# axiom_beta_sensor_cmv12000_v0_9_a57a812d.net
KiCad netlist of a schematic drawn in EAGLE
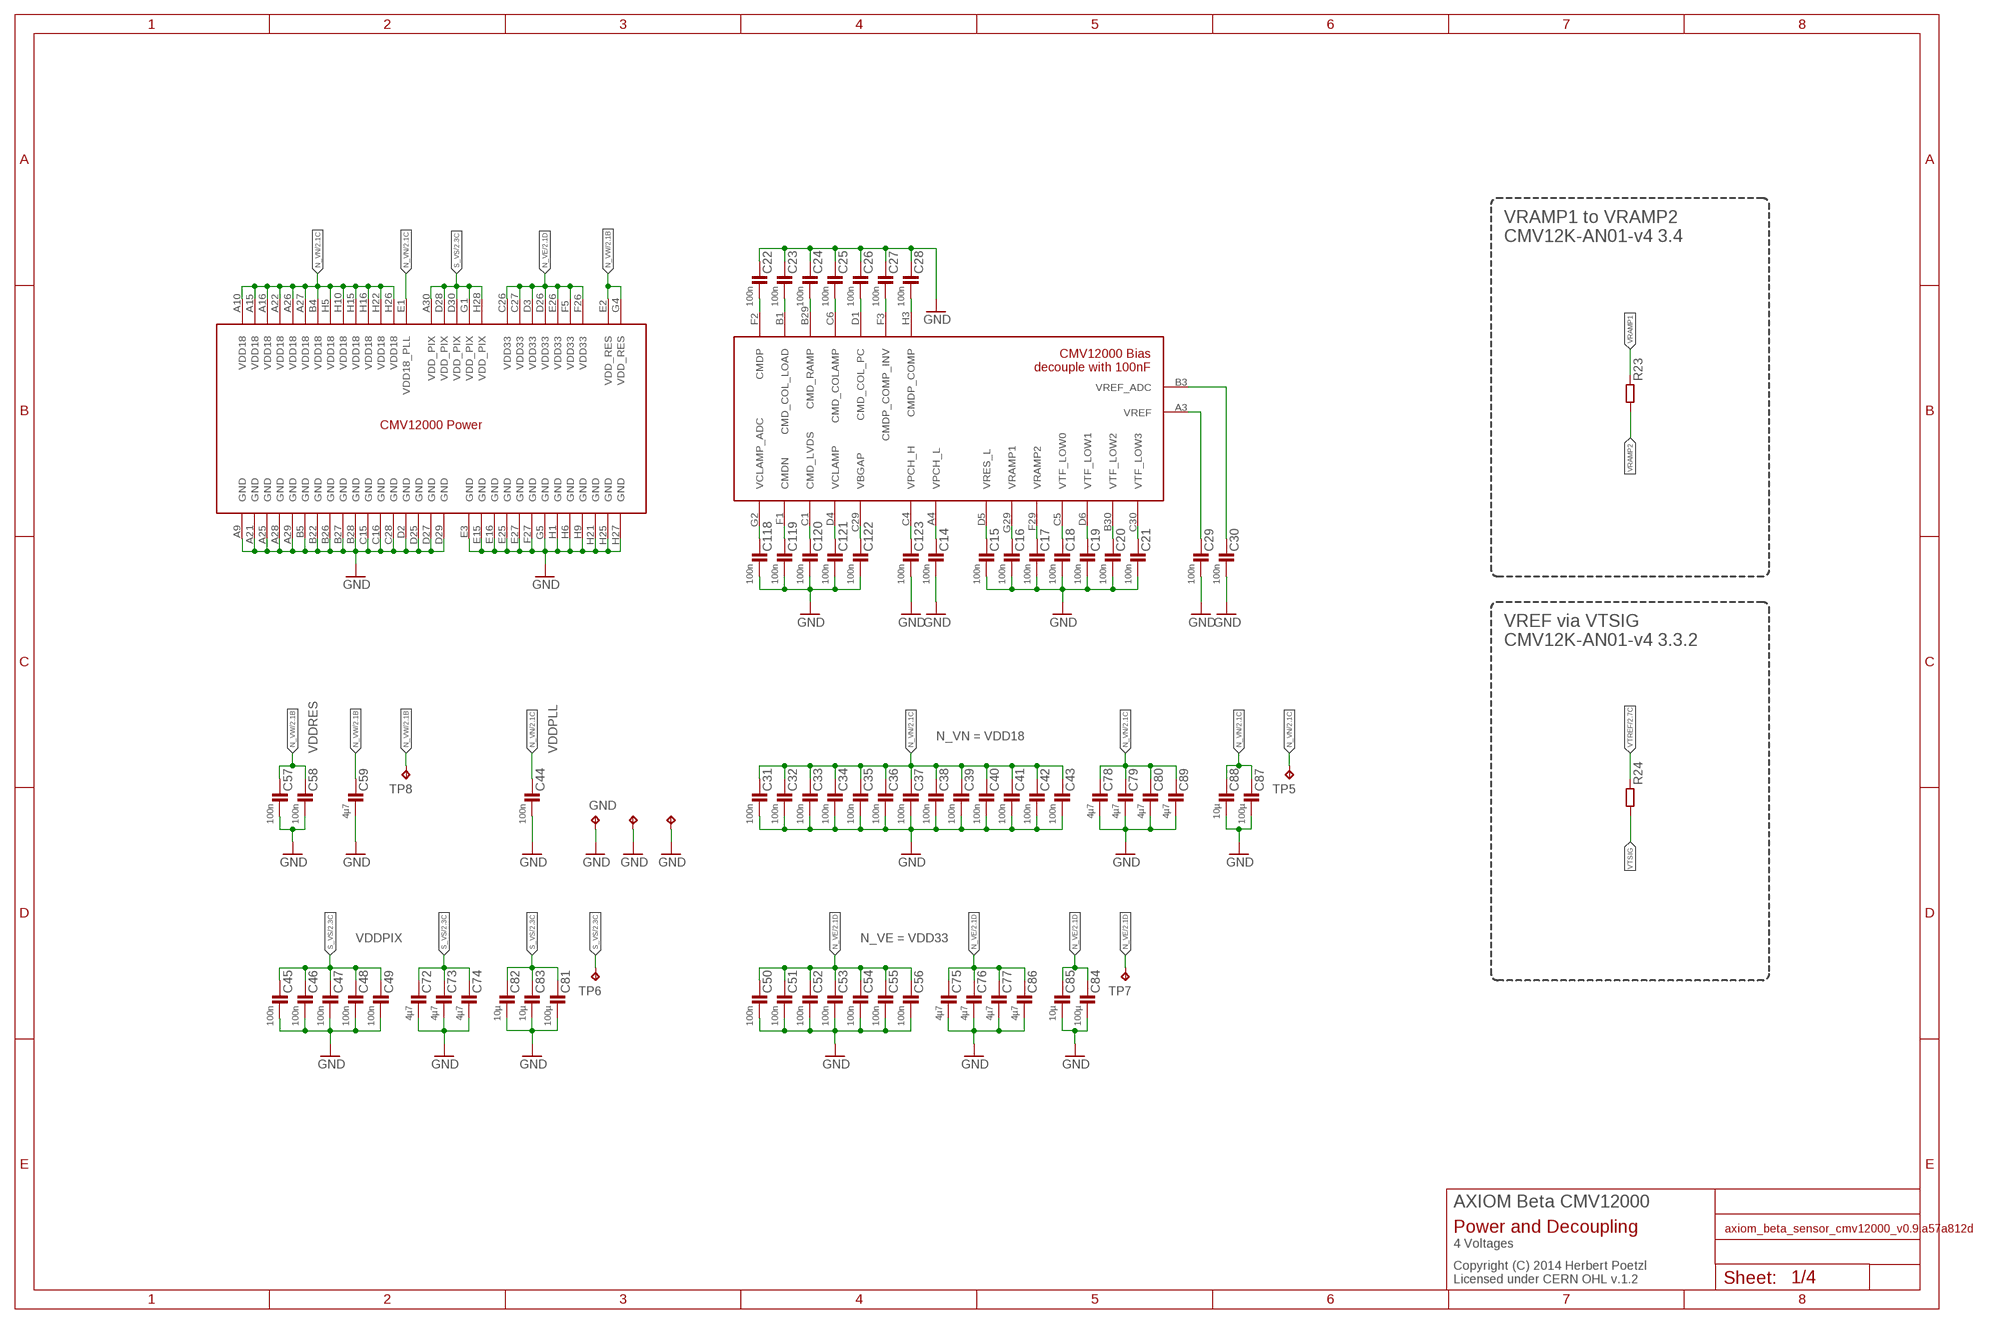
[diagram p0: schematic, sheet 1]
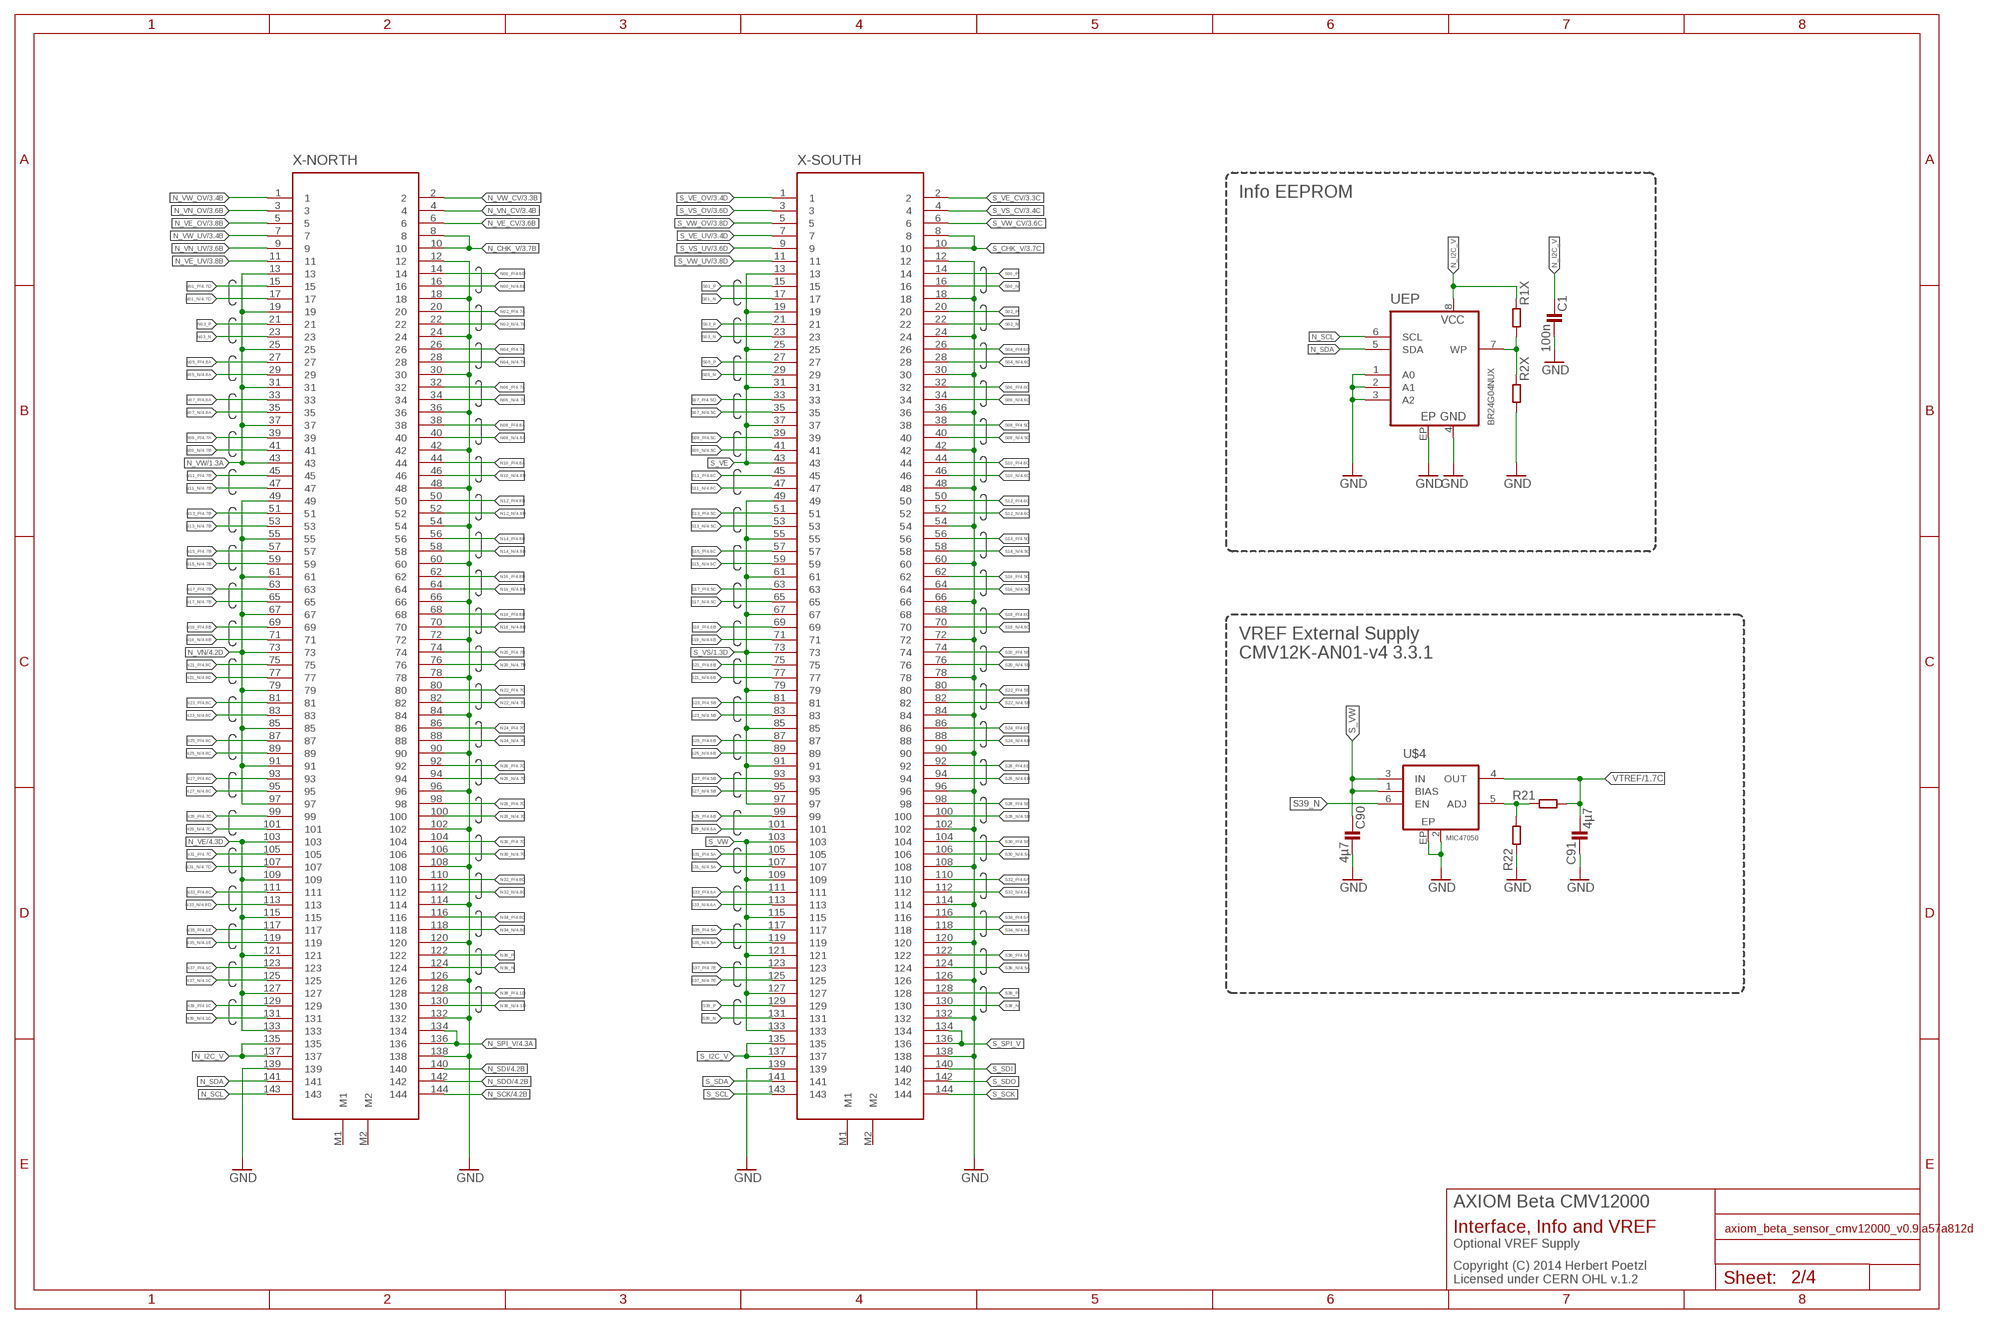
[diagram p1: schematic, sheet 2]
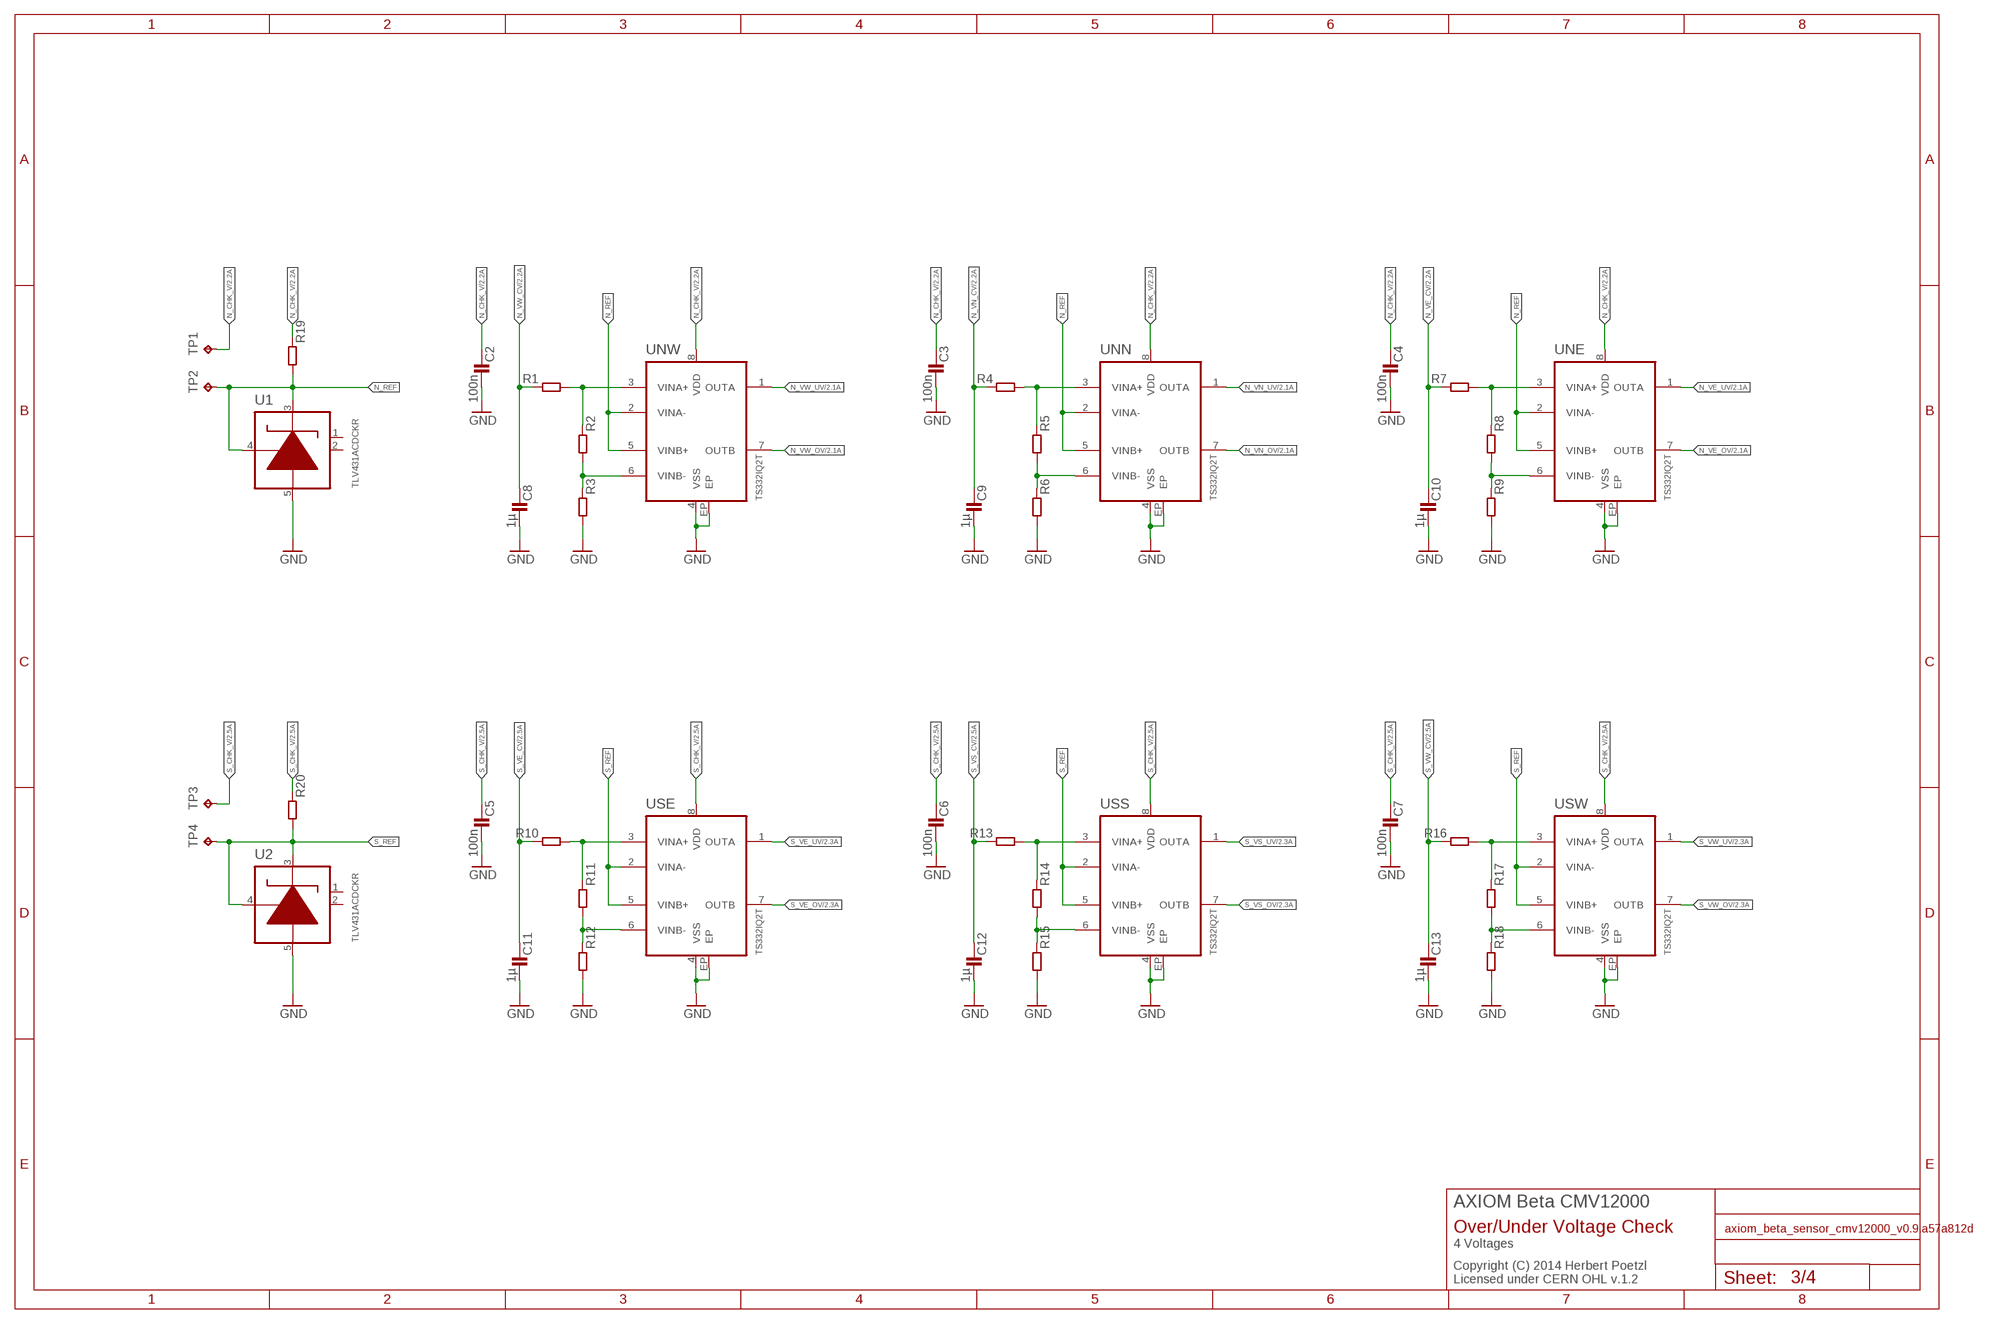
[diagram p2: schematic, sheet 3]
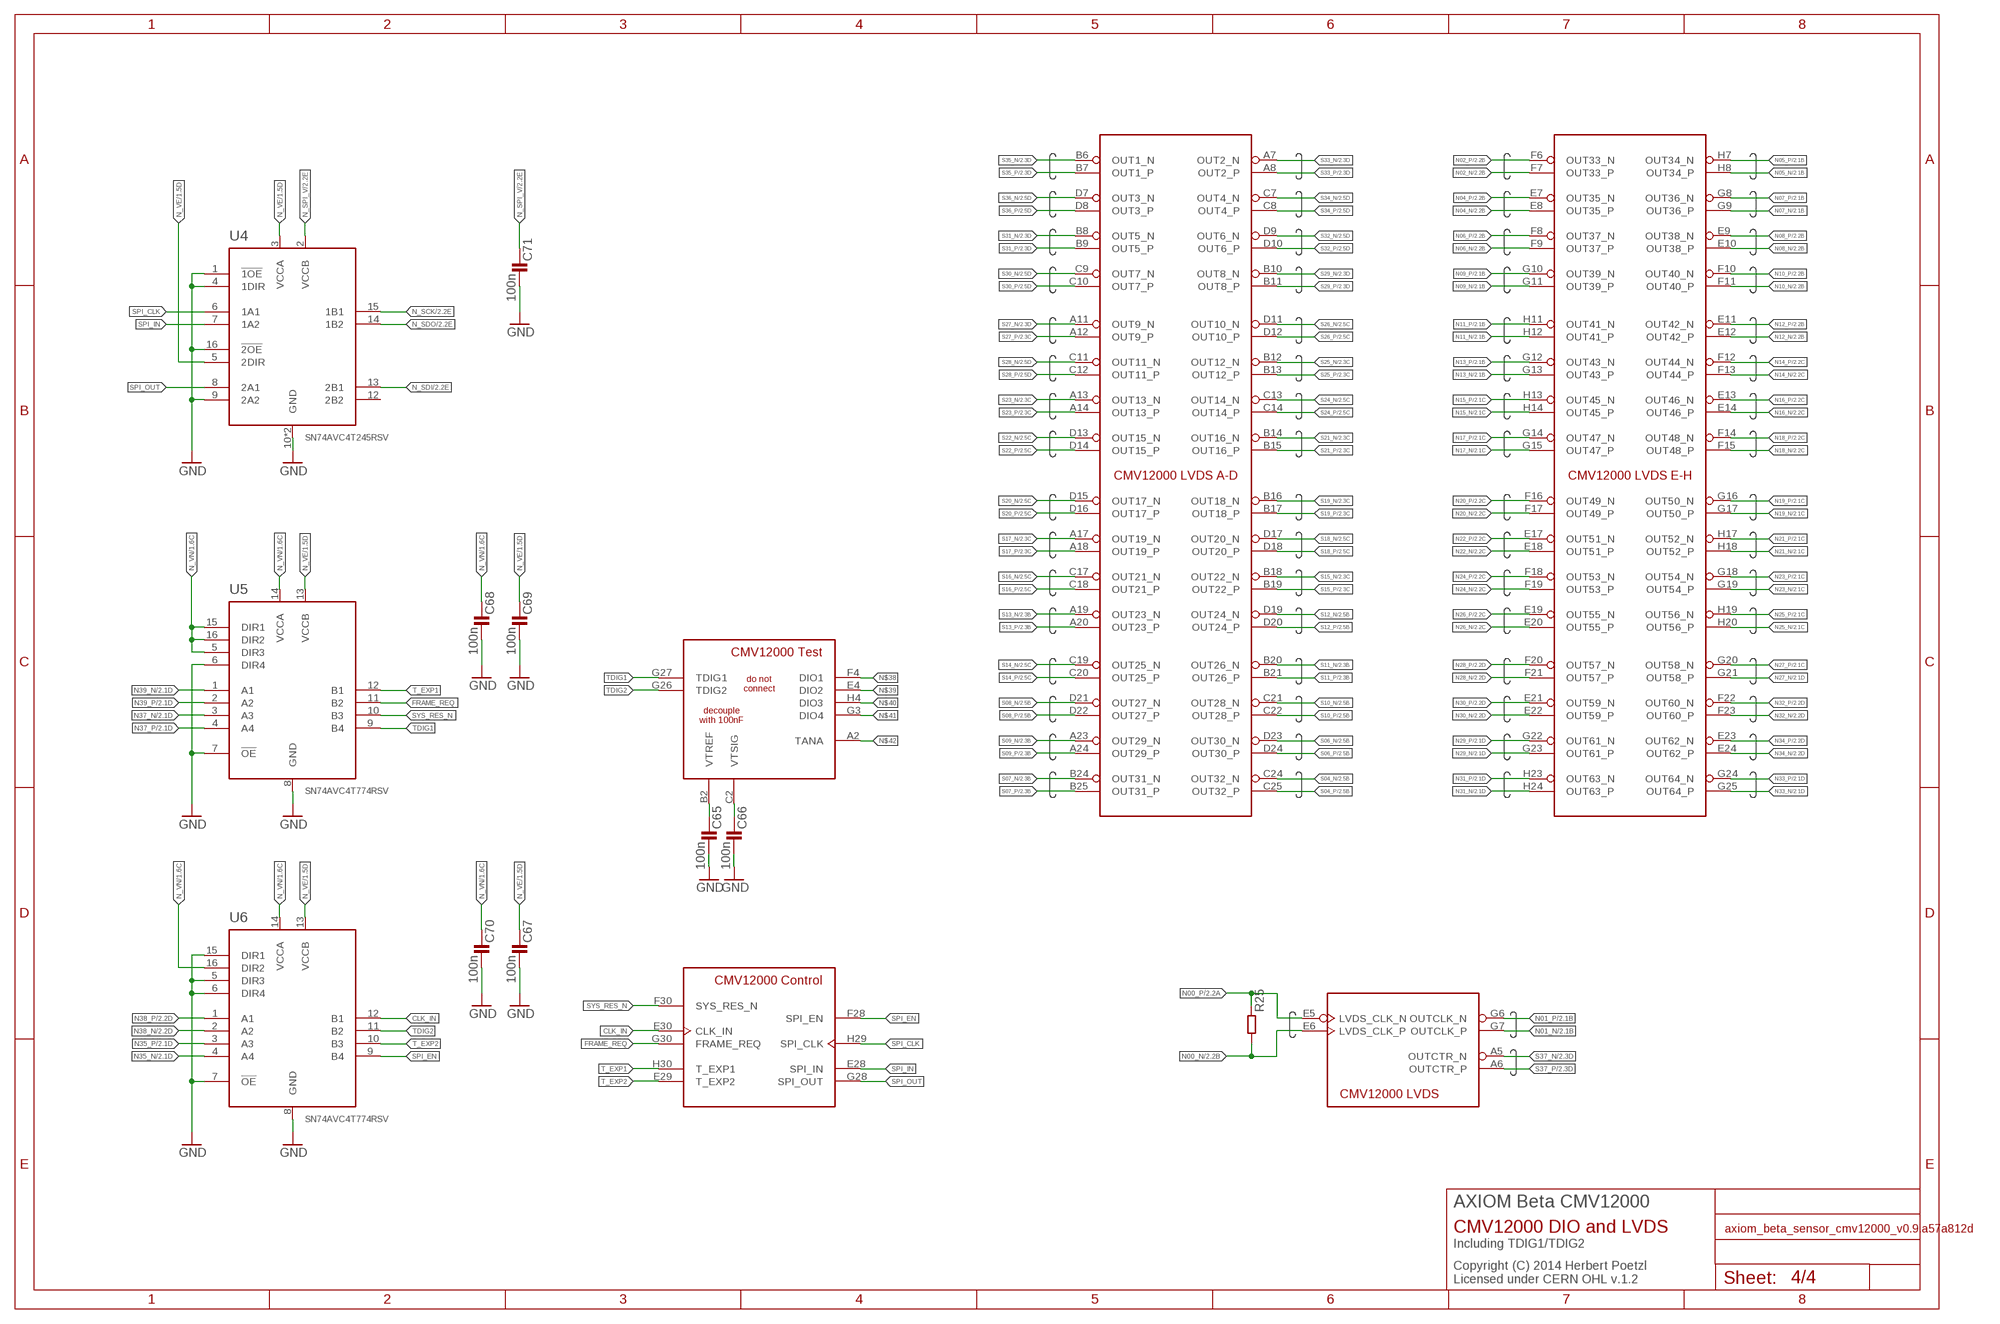
[diagram p3: schematic, sheet 4]

(export (version "E")
  (design (tool "Eeschema 10.0.6"))
  (components
    (comp (ref "C1")
      (value "100n")
      (footprint "eagle-import:0402-C")
      (libsource (lib "eagle-import") (part "C0402-C"))
    )
    (comp (ref "C90")
      (value "4µ7")
      (footprint "eagle-import:0402-C")
      (libsource (lib "eagle-import") (part "C0402-C"))
    )
    (comp (ref "C91")
      (value "4µ7")
      (footprint "eagle-import:0402-C")
      (libsource (lib "eagle-import") (part "C0402-C"))
    )
    (comp (ref "R1X")
      (value "R0402-C")
      (footprint "eagle-import:0402-C")
      (libsource (lib "eagle-import") (part "R0402-C"))
    )
    (comp (ref "R2X")
      (value "R0402-C")
      (footprint "eagle-import:0402-C")
      (libsource (lib "eagle-import") (part "R0402-C"))
    )
    (comp (ref "R21")
      (value "R0402-C")
      (footprint "eagle-import:0402-C")
      (libsource (lib "eagle-import") (part "R0402-C"))
    )
    (comp (ref "R22")
      (value "R0402-C")
      (footprint "eagle-import:0402-C")
      (libsource (lib "eagle-import") (part "R0402-C"))
    )
    (comp (ref "U$4")
      (value "MIC47050")
      (footprint "eagle-import:MLF-6")
      (libsource (lib "eagle-import") (part "MIC47050-ADJ"))
    )
    (comp (ref "UEP")
      (value "BR24G04NUX")
      (footprint "eagle-import:DFN200X300X100-9N")
      (libsource (lib "eagle-import") (part "BR24G04NUX"))
    )
    (comp (ref "X-NORTH")
      (value "FX10-144P")
      (footprint "eagle-import:FX10A-144P")
      (libsource (lib "eagle-import") (part "FX10-144P"))
    )
    (comp (ref "X-SOUTH")
      (value "FX10-144P")
      (footprint "eagle-import:FX10A-144P")
      (libsource (lib "eagle-import") (part "FX10-144P"))
    )
    (comp (ref "C65")
      (value "100n")
      (footprint "eagle-import:0402-C")
      (libsource (lib "eagle-import") (part "C0402-C"))
    )
    (comp (ref "C66")
      (value "100n")
      (footprint "eagle-import:0402-C")
      (libsource (lib "eagle-import") (part "C0402-C"))
    )
    (comp (ref "C67")
      (value "100n")
      (footprint "eagle-import:0402-C")
      (libsource (lib "eagle-import") (part "C0402-C"))
    )
    (comp (ref "C68")
      (value "100n")
      (footprint "eagle-import:0402-C")
      (libsource (lib "eagle-import") (part "C0402-C"))
    )
    (comp (ref "C69")
      (value "100n")
      (footprint "eagle-import:0402-C")
      (libsource (lib "eagle-import") (part "C0402-C"))
    )
    (comp (ref "C70")
      (value "100n")
      (footprint "eagle-import:0402-C")
      (libsource (lib "eagle-import") (part "C0402-C"))
    )
    (comp (ref "C71")
      (value "100n")
      (footprint "eagle-import:0402-C")
      (libsource (lib "eagle-import") (part "C0402-C"))
    )
    (comp (ref "R25")
      (value "R0402-C")
      (footprint "eagle-import:0402-C")
      (libsource (lib "eagle-import") (part "R0402-C"))
    )
    (comp (ref "U$2")
      (value "CMV12000ANDON")
      (footprint "eagle-import:10-30-07-237-400T4")
      (libsource (lib "eagle-import") (part "CMV12000ANDON"))
    )
    (comp (ref "U4")
      (value "SN74AVC4T245RSV")
      (footprint "eagle-import:QFN40P185X265X55-16N")
      (libsource (lib "eagle-import") (part "SN74AVC4T245RSV"))
    )
    (comp (ref "U5")
      (value "SN74AVC4T774RSV")
      (footprint "eagle-import:QFN40P185X265X55-16N")
      (libsource (lib "eagle-import") (part "SN74AVC4T774RSV"))
    )
    (comp (ref "U6")
      (value "SN74AVC4T774RSV")
      (footprint "eagle-import:QFN40P185X265X55-16N")
      (libsource (lib "eagle-import") (part "SN74AVC4T774RSV"))
    )
    (comp (ref "C2")
      (value "100n")
      (footprint "eagle-import:0402-C")
      (libsource (lib "eagle-import") (part "C0402-C"))
    )
    (comp (ref "C3")
      (value "100n")
      (footprint "eagle-import:0402-C")
      (libsource (lib "eagle-import") (part "C0402-C"))
    )
    (comp (ref "C4")
      (value "100n")
      (footprint "eagle-import:0402-C")
      (libsource (lib "eagle-import") (part "C0402-C"))
    )
    (comp (ref "C5")
      (value "100n")
      (footprint "eagle-import:0402-C")
      (libsource (lib "eagle-import") (part "C0402-C"))
    )
    (comp (ref "C6")
      (value "100n")
      (footprint "eagle-import:0402-C")
      (libsource (lib "eagle-import") (part "C0402-C"))
    )
    (comp (ref "C7")
      (value "100n")
      (footprint "eagle-import:0402-C")
      (libsource (lib "eagle-import") (part "C0402-C"))
    )
    (comp (ref "C8")
      (value "1µ")
      (footprint "eagle-import:0402-C")
      (libsource (lib "eagle-import") (part "C0402-C"))
    )
    (comp (ref "C9")
      (value "1µ")
      (footprint "eagle-import:0402-C")
      (libsource (lib "eagle-import") (part "C0402-C"))
    )
    (comp (ref "C10")
      (value "1µ")
      (footprint "eagle-import:0402-C")
      (libsource (lib "eagle-import") (part "C0402-C"))
    )
    (comp (ref "C11")
      (value "1µ")
      (footprint "eagle-import:0402-C")
      (libsource (lib "eagle-import") (part "C0402-C"))
    )
    (comp (ref "C12")
      (value "1µ")
      (footprint "eagle-import:0402-C")
      (libsource (lib "eagle-import") (part "C0402-C"))
    )
    (comp (ref "C13")
      (value "1µ")
      (footprint "eagle-import:0402-C")
      (libsource (lib "eagle-import") (part "C0402-C"))
    )
    (comp (ref "R1")
      (value "R0402-C")
      (footprint "eagle-import:0402-C")
      (libsource (lib "eagle-import") (part "R0402-C"))
    )
    (comp (ref "R2")
      (value "R0402-C")
      (footprint "eagle-import:0402-C")
      (libsource (lib "eagle-import") (part "R0402-C"))
    )
    (comp (ref "R3")
      (value "R0402-C")
      (footprint "eagle-import:0402-C")
      (libsource (lib "eagle-import") (part "R0402-C"))
    )
    (comp (ref "R4")
      (value "R0402-C")
      (footprint "eagle-import:0402-C")
      (libsource (lib "eagle-import") (part "R0402-C"))
    )
    (comp (ref "R5")
      (value "R0402-C")
      (footprint "eagle-import:0402-C")
      (libsource (lib "eagle-import") (part "R0402-C"))
    )
    (comp (ref "R6")
      (value "R0402-C")
      (footprint "eagle-import:0402-C")
      (libsource (lib "eagle-import") (part "R0402-C"))
    )
    (comp (ref "R7")
      (value "R0402-C")
      (footprint "eagle-import:0402-C")
      (libsource (lib "eagle-import") (part "R0402-C"))
    )
    (comp (ref "R8")
      (value "R0402-C")
      (footprint "eagle-import:0402-C")
      (libsource (lib "eagle-import") (part "R0402-C"))
    )
    (comp (ref "R9")
      (value "R0402-C")
      (footprint "eagle-import:0402-C")
      (libsource (lib "eagle-import") (part "R0402-C"))
    )
    (comp (ref "R10")
      (value "R0402-C")
      (footprint "eagle-import:0402-C")
      (libsource (lib "eagle-import") (part "R0402-C"))
    )
    (comp (ref "R11")
      (value "R0402-C")
      (footprint "eagle-import:0402-C")
      (libsource (lib "eagle-import") (part "R0402-C"))
    )
    (comp (ref "R12")
      (value "R0402-C")
      (footprint "eagle-import:0402-C")
      (libsource (lib "eagle-import") (part "R0402-C"))
    )
    (comp (ref "R13")
      (value "R0402-C")
      (footprint "eagle-import:0402-C")
      (libsource (lib "eagle-import") (part "R0402-C"))
    )
    (comp (ref "R14")
      (value "R0402-C")
      (footprint "eagle-import:0402-C")
      (libsource (lib "eagle-import") (part "R0402-C"))
    )
    (comp (ref "R15")
      (value "R0402-C")
      (footprint "eagle-import:0402-C")
      (libsource (lib "eagle-import") (part "R0402-C"))
    )
    (comp (ref "R16")
      (value "R0402-C")
      (footprint "eagle-import:0402-C")
      (libsource (lib "eagle-import") (part "R0402-C"))
    )
    (comp (ref "R17")
      (value "R0402-C")
      (footprint "eagle-import:0402-C")
      (libsource (lib "eagle-import") (part "R0402-C"))
    )
    (comp (ref "R18")
      (value "R0402-C")
      (footprint "eagle-import:0402-C")
      (libsource (lib "eagle-import") (part "R0402-C"))
    )
    (comp (ref "R19")
      (value "R0402-C")
      (footprint "eagle-import:0402-C")
      (libsource (lib "eagle-import") (part "R0402-C"))
    )
    (comp (ref "R20")
      (value "R0402-C")
      (footprint "eagle-import:0402-C")
      (libsource (lib "eagle-import") (part "R0402-C"))
    )
    (comp (ref "TP1")
      (value "TPTP10R")
      (footprint "eagle-import:TP10R")
      (libsource (lib "eagle-import") (part "TPTP10R"))
    )
    (comp (ref "TP2")
      (value "TPTP10R")
      (footprint "eagle-import:TP10R")
      (libsource (lib "eagle-import") (part "TPTP10R"))
    )
    (comp (ref "TP3")
      (value "TPTP10R")
      (footprint "eagle-import:TP10R")
      (libsource (lib "eagle-import") (part "TPTP10R"))
    )
    (comp (ref "TP4")
      (value "TPTP10R")
      (footprint "eagle-import:TP10R")
      (libsource (lib "eagle-import") (part "TPTP10R"))
    )
    (comp (ref "U1")
      (value "TLV431ACDCKR")
      (footprint "eagle-import:SOT65P210X110-5N")
      (libsource (lib "eagle-import") (part "TLV431ACDCKR"))
    )
    (comp (ref "U2")
      (value "TLV431ACDCKR")
      (footprint "eagle-import:SOT65P210X110-5N")
      (libsource (lib "eagle-import") (part "TLV431ACDCKR"))
    )
    (comp (ref "UNE")
      (value "TS332IQ2T")
      (footprint "eagle-import:DFN200X200X100-9N")
      (libsource (lib "eagle-import") (part "TS332IQ2T"))
    )
    (comp (ref "UNN")
      (value "TS332IQ2T")
      (footprint "eagle-import:DFN200X200X100-9N")
      (libsource (lib "eagle-import") (part "TS332IQ2T"))
    )
    (comp (ref "UNW")
      (value "TS332IQ2T")
      (footprint "eagle-import:DFN200X200X100-9N")
      (libsource (lib "eagle-import") (part "TS332IQ2T"))
    )
    (comp (ref "USE")
      (value "TS332IQ2T")
      (footprint "eagle-import:DFN200X200X100-9N")
      (libsource (lib "eagle-import") (part "TS332IQ2T"))
    )
    (comp (ref "USS")
      (value "TS332IQ2T")
      (footprint "eagle-import:DFN200X200X100-9N")
      (libsource (lib "eagle-import") (part "TS332IQ2T"))
    )
    (comp (ref "USW")
      (value "TS332IQ2T")
      (footprint "eagle-import:DFN200X200X100-9N")
      (libsource (lib "eagle-import") (part "TS332IQ2T"))
    )
    (comp (ref "C14")
      (value "100n")
      (footprint "eagle-import:0402-C")
      (libsource (lib "eagle-import") (part "C0402-C"))
    )
    (comp (ref "C15")
      (value "100n")
      (footprint "eagle-import:0402-C")
      (libsource (lib "eagle-import") (part "C0402-C"))
    )
    (comp (ref "C16")
      (value "100n")
      (footprint "eagle-import:0402-C")
      (libsource (lib "eagle-import") (part "C0402-C"))
    )
    (comp (ref "C17")
      (value "100n")
      (footprint "eagle-import:0402-C")
      (libsource (lib "eagle-import") (part "C0402-C"))
    )
    (comp (ref "C18")
      (value "100n")
      (footprint "eagle-import:0402-C")
      (libsource (lib "eagle-import") (part "C0402-C"))
    )
    (comp (ref "C19")
      (value "100n")
      (footprint "eagle-import:0402-C")
      (libsource (lib "eagle-import") (part "C0402-C"))
    )
    (comp (ref "C20")
      (value "100n")
      (footprint "eagle-import:0402-C")
      (libsource (lib "eagle-import") (part "C0402-C"))
    )
    (comp (ref "C21")
      (value "100n")
      (footprint "eagle-import:0402-C")
      (libsource (lib "eagle-import") (part "C0402-C"))
    )
    (comp (ref "C22")
      (value "100n")
      (footprint "eagle-import:0402-C")
      (libsource (lib "eagle-import") (part "C0402-C"))
    )
    (comp (ref "C23")
      (value "100n")
      (footprint "eagle-import:0402-C")
      (libsource (lib "eagle-import") (part "C0402-C"))
    )
    (comp (ref "C24")
      (value "100n")
      (footprint "eagle-import:0402-C")
      (libsource (lib "eagle-import") (part "C0402-C"))
    )
    (comp (ref "C25")
      (value "100n")
      (footprint "eagle-import:0402-C")
      (libsource (lib "eagle-import") (part "C0402-C"))
    )
    (comp (ref "C26")
      (value "100n")
      (footprint "eagle-import:0402-C")
      (libsource (lib "eagle-import") (part "C0402-C"))
    )
    (comp (ref "C27")
      (value "100n")
      (footprint "eagle-import:0402-C")
      (libsource (lib "eagle-import") (part "C0402-C"))
    )
    (comp (ref "C28")
      (value "100n")
      (footprint "eagle-import:0402-C")
      (libsource (lib "eagle-import") (part "C0402-C"))
    )
    (comp (ref "C29")
      (value "100n")
      (footprint "eagle-import:0402-C")
      (libsource (lib "eagle-import") (part "C0402-C"))
    )
    (comp (ref "C30")
      (value "100n")
      (footprint "eagle-import:0402-C")
      (libsource (lib "eagle-import") (part "C0402-C"))
    )
    (comp (ref "C31")
      (value "100n")
      (footprint "eagle-import:0402-C")
      (libsource (lib "eagle-import") (part "C0402-C"))
    )
    (comp (ref "C32")
      (value "100n")
      (footprint "eagle-import:0402-C")
      (libsource (lib "eagle-import") (part "C0402-C"))
    )
    (comp (ref "C33")
      (value "100n")
      (footprint "eagle-import:0402-C")
      (libsource (lib "eagle-import") (part "C0402-C"))
    )
    (comp (ref "C34")
      (value "100n")
      (footprint "eagle-import:0402-C")
      (libsource (lib "eagle-import") (part "C0402-C"))
    )
    (comp (ref "C35")
      (value "100n")
      (footprint "eagle-import:0402-C")
      (libsource (lib "eagle-import") (part "C0402-C"))
    )
    (comp (ref "C36")
      (value "100n")
      (footprint "eagle-import:0402-C")
      (libsource (lib "eagle-import") (part "C0402-C"))
    )
    (comp (ref "C37")
      (value "100n")
      (footprint "eagle-import:0402-C")
      (libsource (lib "eagle-import") (part "C0402-C"))
    )
    (comp (ref "C38")
      (value "100n")
      (footprint "eagle-import:0402-C")
      (libsource (lib "eagle-import") (part "C0402-C"))
    )
    (comp (ref "C39")
      (value "100n")
      (footprint "eagle-import:0402-C")
      (libsource (lib "eagle-import") (part "C0402-C"))
    )
    (comp (ref "C40")
      (value "100n")
      (footprint "eagle-import:0402-C")
      (libsource (lib "eagle-import") (part "C0402-C"))
    )
    (comp (ref "C41")
      (value "100n")
      (footprint "eagle-import:0402-C")
      (libsource (lib "eagle-import") (part "C0402-C"))
    )
    (comp (ref "C42")
      (value "100n")
      (footprint "eagle-import:0402-C")
      (libsource (lib "eagle-import") (part "C0402-C"))
    )
    (comp (ref "C43")
      (value "100n")
      (footprint "eagle-import:0402-C")
      (libsource (lib "eagle-import") (part "C0402-C"))
    )
    (comp (ref "C44")
      (value "100n")
      (footprint "eagle-import:0402-C")
      (libsource (lib "eagle-import") (part "C0402-C"))
    )
    (comp (ref "C45")
      (value "100n")
      (footprint "eagle-import:0402-C")
      (libsource (lib "eagle-import") (part "C0402-C"))
    )
    (comp (ref "C46")
      (value "100n")
      (footprint "eagle-import:0402-C")
      (libsource (lib "eagle-import") (part "C0402-C"))
    )
    (comp (ref "C47")
      (value "100n")
      (footprint "eagle-import:0402-C")
      (libsource (lib "eagle-import") (part "C0402-C"))
    )
    (comp (ref "C48")
      (value "100n")
      (footprint "eagle-import:0402-C")
      (libsource (lib "eagle-import") (part "C0402-C"))
    )
    (comp (ref "C49")
      (value "100n")
      (footprint "eagle-import:0402-C")
      (libsource (lib "eagle-import") (part "C0402-C"))
    )
    (comp (ref "C50")
      (value "100n")
      (footprint "eagle-import:0402-C")
      (libsource (lib "eagle-import") (part "C0402-C"))
    )
    (comp (ref "C51")
      (value "100n")
      (footprint "eagle-import:0402-C")
      (libsource (lib "eagle-import") (part "C0402-C"))
    )
    (comp (ref "C52")
      (value "100n")
      (footprint "eagle-import:0402-C")
      (libsource (lib "eagle-import") (part "C0402-C"))
    )
    (comp (ref "C53")
      (value "100n")
      (footprint "eagle-import:0402-C")
      (libsource (lib "eagle-import") (part "C0402-C"))
    )
    (comp (ref "C54")
      (value "100n")
      (footprint "eagle-import:0402-C")
      (libsource (lib "eagle-import") (part "C0402-C"))
    )
    (comp (ref "C55")
      (value "100n")
      (footprint "eagle-import:0402-C")
      (libsource (lib "eagle-import") (part "C0402-C"))
    )
    (comp (ref "C56")
      (value "100n")
      (footprint "eagle-import:0402-C")
      (libsource (lib "eagle-import") (part "C0402-C"))
    )
    (comp (ref "C57")
      (value "100n")
      (footprint "eagle-import:0402-C")
      (libsource (lib "eagle-import") (part "C0402-C"))
    )
    (comp (ref "C58")
      (value "100n")
      (footprint "eagle-import:0402-C")
      (libsource (lib "eagle-import") (part "C0402-C"))
    )
    (comp (ref "C59")
      (value "4µ7")
      (footprint "eagle-import:0402-C")
      (libsource (lib "eagle-import") (part "C0402-C"))
    )
    (comp (ref "C72")
      (value "4µ7")
      (footprint "eagle-import:0402-B")
      (libsource (lib "eagle-import") (part "C0402-B"))
    )
    (comp (ref "C73")
      (value "4µ7")
      (footprint "eagle-import:0402-C")
      (libsource (lib "eagle-import") (part "C0402-C"))
    )
    (comp (ref "C74")
      (value "4µ7")
      (footprint "eagle-import:0402-C")
      (libsource (lib "eagle-import") (part "C0402-C"))
    )
    (comp (ref "C75")
      (value "4µ7")
      (footprint "eagle-import:0402-C")
      (libsource (lib "eagle-import") (part "C0402-C"))
    )
    (comp (ref "C76")
      (value "4µ7")
      (footprint "eagle-import:0402-C")
      (libsource (lib "eagle-import") (part "C0402-C"))
    )
    (comp (ref "C77")
      (value "4µ7")
      (footprint "eagle-import:0402-B")
      (libsource (lib "eagle-import") (part "C0402-B"))
    )
    (comp (ref "C78")
      (value "4µ7")
      (footprint "eagle-import:0402-B")
      (libsource (lib "eagle-import") (part "C0402-B"))
    )
    (comp (ref "C79")
      (value "4µ7")
      (footprint "eagle-import:0402-C")
      (libsource (lib "eagle-import") (part "C0402-C"))
    )
    (comp (ref "C80")
      (value "4µ7")
      (footprint "eagle-import:0402-C")
      (libsource (lib "eagle-import") (part "C0402-C"))
    )
    (comp (ref "C81")
      (value "100µ")
      (footprint "eagle-import:1206-B")
      (libsource (lib "eagle-import") (part "C1206-B"))
    )
    (comp (ref "C82")
      (value "10µ")
      (footprint "eagle-import:0603-C")
      (libsource (lib "eagle-import") (part "C0603-C"))
    )
    (comp (ref "C83")
      (value "10µ")
      (footprint "eagle-import:0603-C")
      (libsource (lib "eagle-import") (part "C0603-C"))
    )
    (comp (ref "C84")
      (value "100µ")
      (footprint "eagle-import:1206-B")
      (libsource (lib "eagle-import") (part "C1206-B"))
    )
    (comp (ref "C85")
      (value "10µ")
      (footprint "eagle-import:0603-C")
      (libsource (lib "eagle-import") (part "C0603-C"))
    )
    (comp (ref "C86")
      (value "4µ7")
      (footprint "eagle-import:0402-C")
      (libsource (lib "eagle-import") (part "C0402-C"))
    )
    (comp (ref "C87")
      (value "100µ")
      (footprint "eagle-import:1206-B")
      (libsource (lib "eagle-import") (part "C1206-B"))
    )
    (comp (ref "C88")
      (value "10µ")
      (footprint "eagle-import:0603-C")
      (libsource (lib "eagle-import") (part "C0603-C"))
    )
    (comp (ref "C89")
      (value "4µ7")
      (footprint "eagle-import:0402-C")
      (libsource (lib "eagle-import") (part "C0402-C"))
    )
    (comp (ref "C118")
      (value "100n")
      (footprint "eagle-import:0402-C")
      (libsource (lib "eagle-import") (part "C0402-C"))
    )
    (comp (ref "C119")
      (value "100n")
      (footprint "eagle-import:0402-C")
      (libsource (lib "eagle-import") (part "C0402-C"))
    )
    (comp (ref "C120")
      (value "100n")
      (footprint "eagle-import:0402-C")
      (libsource (lib "eagle-import") (part "C0402-C"))
    )
    (comp (ref "C121")
      (value "100n")
      (footprint "eagle-import:0402-C")
      (libsource (lib "eagle-import") (part "C0402-C"))
    )
    (comp (ref "C122")
      (value "100n")
      (footprint "eagle-import:0402-C")
      (libsource (lib "eagle-import") (part "C0402-C"))
    )
    (comp (ref "C123")
      (value "100n")
      (footprint "eagle-import:0402-C")
      (libsource (lib "eagle-import") (part "C0402-C"))
    )
    (comp (ref "GND")
      (value "TPTP10R")
      (footprint "eagle-import:TP10R")
      (libsource (lib "eagle-import") (part "TPTP10R"))
    )
    (comp (ref "GND75")
      (value "TPTP10R")
      (footprint "eagle-import:TP10R")
      (libsource (lib "eagle-import") (part "TPTP10R"))
    )
    (comp (ref "GND77")
      (value "TPTP10R")
      (footprint "eagle-import:TP10R")
      (libsource (lib "eagle-import") (part "TPTP10R"))
    )
    (comp (ref "R23")
      (value "R0402-C")
      (footprint "eagle-import:0402-C")
      (libsource (lib "eagle-import") (part "R0402-C"))
    )
    (comp (ref "R24")
      (value "R0402-C")
      (footprint "eagle-import:0402-C")
      (libsource (lib "eagle-import") (part "R0402-C"))
    )
    (comp (ref "TP5")
      (value "TPTP10R")
      (footprint "eagle-import:TP10R")
      (libsource (lib "eagle-import") (part "TPTP10R"))
    )
    (comp (ref "TP6")
      (value "TPTP10R")
      (footprint "eagle-import:TP10R")
      (libsource (lib "eagle-import") (part "TPTP10R"))
    )
    (comp (ref "TP7")
      (value "TPTP10R")
      (footprint "eagle-import:TP10R")
      (libsource (lib "eagle-import") (part "TPTP10R"))
    )
    (comp (ref "TP8")
      (value "TPTP10R")
      (footprint "eagle-import:TP10R")
      (libsource (lib "eagle-import") (part "TPTP10R"))
    )
  )
  (nets
    (net (code "1") (name "CLK_IN") (class "Default")
      (node (ref "U$2") (pin "E30") (pinfunction "CLK_IN_E30") (pintype "input"))
      (node (ref "U6") (pin "12") (pinfunction "B1_12") (pintype "bidirectional"))
    )
    (net (code "2") (name "FRAME_REQ") (class "Default")
      (node (ref "U$2") (pin "G30") (pinfunction "FRAME_REQ_G30") (pintype "input"))
      (node (ref "U5") (pin "11") (pinfunction "B2_11") (pintype "bidirectional"))
    )
    (net (code "3") (name "GND") (class "Default")
      (node (ref "C1") (pin "2") (pinfunction "2_2") (pintype "passive"))
      (node (ref "C10") (pin "2") (pinfunction "2_2") (pintype "passive"))
      (node (ref "C11") (pin "2") (pinfunction "2_2") (pintype "passive"))
      (node (ref "C118") (pin "2") (pinfunction "2_2") (pintype "passive"))
      (node (ref "C119") (pin "2") (pinfunction "2_2") (pintype "passive"))
      (node (ref "C12") (pin "2") (pinfunction "2_2") (pintype "passive"))
      (node (ref "C120") (pin "2") (pinfunction "2_2") (pintype "passive"))
      (node (ref "C121") (pin "2") (pinfunction "2_2") (pintype "passive"))
      (node (ref "C122") (pin "2") (pinfunction "2_2") (pintype "passive"))
      (node (ref "C123") (pin "2") (pinfunction "2_2") (pintype "passive"))
      (node (ref "C13") (pin "2") (pinfunction "2_2") (pintype "passive"))
      (node (ref "C14") (pin "2") (pinfunction "2_2") (pintype "passive"))
      (node (ref "C15") (pin "2") (pinfunction "2_2") (pintype "passive"))
      (node (ref "C16") (pin "2") (pinfunction "2_2") (pintype "passive"))
      (node (ref "C17") (pin "2") (pinfunction "2_2") (pintype "passive"))
      (node (ref "C18") (pin "2") (pinfunction "2_2") (pintype "passive"))
      (node (ref "C19") (pin "2") (pinfunction "2_2") (pintype "passive"))
      (node (ref "C2") (pin "2") (pinfunction "2_2") (pintype "passive"))
      (node (ref "C20") (pin "2") (pinfunction "2_2") (pintype "passive"))
      (node (ref "C21") (pin "2") (pinfunction "2_2") (pintype "passive"))
      (node (ref "C22") (pin "1") (pinfunction "1_1") (pintype "passive"))
      (node (ref "C23") (pin "1") (pinfunction "1_1") (pintype "passive"))
      (node (ref "C24") (pin "1") (pinfunction "1_1") (pintype "passive"))
      (node (ref "C25") (pin "1") (pinfunction "1_1") (pintype "passive"))
      (node (ref "C26") (pin "1") (pinfunction "1_1") (pintype "passive"))
      (node (ref "C27") (pin "1") (pinfunction "1_1") (pintype "passive"))
      (node (ref "C28") (pin "1") (pinfunction "1_1") (pintype "passive"))
      (node (ref "C29") (pin "2") (pinfunction "2_2") (pintype "passive"))
      (node (ref "C3") (pin "2") (pinfunction "2_2") (pintype "passive"))
      (node (ref "C30") (pin "2") (pinfunction "2_2") (pintype "passive"))
      (node (ref "C31") (pin "2") (pinfunction "2_2") (pintype "passive"))
      (node (ref "C32") (pin "2") (pinfunction "2_2") (pintype "passive"))
      (node (ref "C33") (pin "2") (pinfunction "2_2") (pintype "passive"))
      (node (ref "C34") (pin "2") (pinfunction "2_2") (pintype "passive"))
      (node (ref "C35") (pin "2") (pinfunction "2_2") (pintype "passive"))
      (node (ref "C36") (pin "2") (pinfunction "2_2") (pintype "passive"))
      (node (ref "C37") (pin "2") (pinfunction "2_2") (pintype "passive"))
      (node (ref "C38") (pin "2") (pinfunction "2_2") (pintype "passive"))
      (node (ref "C39") (pin "2") (pinfunction "2_2") (pintype "passive"))
      (node (ref "C4") (pin "2") (pinfunction "2_2") (pintype "passive"))
      (node (ref "C40") (pin "2") (pinfunction "2_2") (pintype "passive"))
      (node (ref "C41") (pin "2") (pinfunction "2_2") (pintype "passive"))
      (node (ref "C42") (pin "2") (pinfunction "2_2") (pintype "passive"))
      (node (ref "C43") (pin "2") (pinfunction "2_2") (pintype "passive"))
      (node (ref "C44") (pin "2") (pinfunction "2_2") (pintype "passive"))
      (node (ref "C45") (pin "2") (pinfunction "2_2") (pintype "passive"))
      (node (ref "C46") (pin "2") (pinfunction "2_2") (pintype "passive"))
      (node (ref "C47") (pin "2") (pinfunction "2_2") (pintype "passive"))
      (node (ref "C48") (pin "2") (pinfunction "2_2") (pintype "passive"))
      (node (ref "C49") (pin "2") (pinfunction "2_2") (pintype "passive"))
      (node (ref "C5") (pin "2") (pinfunction "2_2") (pintype "passive"))
      (node (ref "C50") (pin "2") (pinfunction "2_2") (pintype "passive"))
      (node (ref "C51") (pin "2") (pinfunction "2_2") (pintype "passive"))
      (node (ref "C52") (pin "2") (pinfunction "2_2") (pintype "passive"))
      (node (ref "C53") (pin "2") (pinfunction "2_2") (pintype "passive"))
      (node (ref "C54") (pin "2") (pinfunction "2_2") (pintype "passive"))
      (node (ref "C55") (pin "2") (pinfunction "2_2") (pintype "passive"))
      (node (ref "C56") (pin "2") (pinfunction "2_2") (pintype "passive"))
      (node (ref "C57") (pin "2") (pinfunction "2_2") (pintype "passive"))
      (node (ref "C58") (pin "2") (pinfunction "2_2") (pintype "passive"))
      (node (ref "C59") (pin "2") (pinfunction "2_2") (pintype "passive"))
      (node (ref "C6") (pin "2") (pinfunction "2_2") (pintype "passive"))
      (node (ref "C65") (pin "2") (pinfunction "2_2") (pintype "passive"))
      (node (ref "C66") (pin "2") (pinfunction "2_2") (pintype "passive"))
      (node (ref "C67") (pin "2") (pinfunction "2_2") (pintype "passive"))
      (node (ref "C68") (pin "2") (pinfunction "2_2") (pintype "passive"))
      (node (ref "C69") (pin "2") (pinfunction "2_2") (pintype "passive"))
      (node (ref "C7") (pin "2") (pinfunction "2_2") (pintype "passive"))
      (node (ref "C70") (pin "2") (pinfunction "2_2") (pintype "passive"))
      (node (ref "C71") (pin "2") (pinfunction "2_2") (pintype "passive"))
      (node (ref "C72") (pin "2") (pinfunction "2_2") (pintype "passive"))
      (node (ref "C73") (pin "2") (pinfunction "2_2") (pintype "passive"))
      (node (ref "C74") (pin "2") (pinfunction "2_2") (pintype "passive"))
      (node (ref "C75") (pin "2") (pinfunction "2_2") (pintype "passive"))
      (node (ref "C76") (pin "2") (pinfunction "2_2") (pintype "passive"))
      (node (ref "C77") (pin "2") (pinfunction "2_2") (pintype "passive"))
      (node (ref "C78") (pin "2") (pinfunction "2_2") (pintype "passive"))
      (node (ref "C79") (pin "2") (pinfunction "2_2") (pintype "passive"))
      (node (ref "C8") (pin "2") (pinfunction "2_2") (pintype "passive"))
      (node (ref "C80") (pin "2") (pinfunction "2_2") (pintype "passive"))
      (node (ref "C81") (pin "2") (pinfunction "2_2") (pintype "passive"))
      (node (ref "C82") (pin "2") (pinfunction "2_2") (pintype "passive"))
      (node (ref "C83") (pin "2") (pinfunction "2_2") (pintype "passive"))
      (node (ref "C84") (pin "2") (pinfunction "2_2") (pintype "passive"))
      (node (ref "C85") (pin "2") (pinfunction "2_2") (pintype "passive"))
      (node (ref "C86") (pin "2") (pinfunction "2_2") (pintype "passive"))
      (node (ref "C87") (pin "2") (pinfunction "2_2") (pintype "passive"))
      (node (ref "C88") (pin "2") (pinfunction "2_2") (pintype "passive"))
      (node (ref "C89") (pin "2") (pinfunction "2_2") (pintype "passive"))
      (node (ref "C9") (pin "2") (pinfunction "2_2") (pintype "passive"))
      (node (ref "C90") (pin "2") (pinfunction "2_2") (pintype "passive"))
      (node (ref "C91") (pin "1") (pinfunction "1_1") (pintype "passive"))
      (node (ref "GND") (pin "TP") (pinfunction "TP_TP") (pintype "input"))
      (node (ref "GND75") (pin "TP") (pinfunction "TP_TP") (pintype "input"))
      (node (ref "GND77") (pin "TP") (pinfunction "TP_TP") (pintype "input"))
      (node (ref "R12") (pin "2") (pinfunction "2_2") (pintype "passive"))
      (node (ref "R15") (pin "2") (pinfunction "2_2") (pintype "passive"))
      (node (ref "R18") (pin "2") (pinfunction "2_2") (pintype "passive"))
      (node (ref "R22") (pin "1") (pinfunction "1_1") (pintype "passive"))
      (node (ref "R2X") (pin "2") (pinfunction "2_2") (pintype "passive"))
      (node (ref "R3") (pin "2") (pinfunction "2_2") (pintype "passive"))
      (node (ref "R6") (pin "2") (pinfunction "2_2") (pintype "passive"))
      (node (ref "R9") (pin "2") (pinfunction "2_2") (pintype "passive"))
      (node (ref "U$2") (pin "A21") (pinfunction "GND_A21") (pintype "power_in"))
      (node (ref "U$2") (pin "A25") (pinfunction "GND_A25") (pintype "power_in"))
      (node (ref "U$2") (pin "A28") (pinfunction "GND_A28") (pintype "power_in"))
      (node (ref "U$2") (pin "A29") (pinfunction "GND_A29") (pintype "power_in"))
      (node (ref "U$2") (pin "A9") (pinfunction "GND_A9") (pintype "power_in"))
      (node (ref "U$2") (pin "B22") (pinfunction "GND_B22") (pintype "power_in"))
      (node (ref "U$2") (pin "B26") (pinfunction "GND_B26") (pintype "power_in"))
      (node (ref "U$2") (pin "B27") (pinfunction "GND_B27") (pintype "power_in"))
      (node (ref "U$2") (pin "B28") (pinfunction "GND_B28") (pintype "power_in"))
      (node (ref "U$2") (pin "B5") (pinfunction "GND_B5") (pintype "power_in"))
      (node (ref "U$2") (pin "C15") (pinfunction "GND_C15") (pintype "power_in"))
      (node (ref "U$2") (pin "C16") (pinfunction "GND_C16") (pintype "power_in"))
      (node (ref "U$2") (pin "C28") (pinfunction "GND_C28") (pintype "power_in"))
      (node (ref "U$2") (pin "D2") (pinfunction "GND_D2") (pintype "power_in"))
      (node (ref "U$2") (pin "D25") (pinfunction "GND_D25") (pintype "power_in"))
      (node (ref "U$2") (pin "D27") (pinfunction "GND_D27") (pintype "power_in"))
      (node (ref "U$2") (pin "D29") (pinfunction "GND_D29") (pintype "power_in"))
      (node (ref "U$2") (pin "E15") (pinfunction "GND_E15") (pintype "power_in"))
      (node (ref "U$2") (pin "E16") (pinfunction "GND_E16") (pintype "power_in"))
      (node (ref "U$2") (pin "E25") (pinfunction "GND_E25") (pintype "power_in"))
      (node (ref "U$2") (pin "E27") (pinfunction "GND_E27") (pintype "power_in"))
      (node (ref "U$2") (pin "E3") (pinfunction "GND_E3") (pintype "power_in"))
      (node (ref "U$2") (pin "F27") (pinfunction "GND_F27") (pintype "power_in"))
      (node (ref "U$2") (pin "G5") (pinfunction "GND_G5") (pintype "power_in"))
      (node (ref "U$2") (pin "H1") (pinfunction "GND_H1") (pintype "power_in"))
      (node (ref "U$2") (pin "H21") (pinfunction "GND_H21") (pintype "power_in"))
      (node (ref "U$2") (pin "H25") (pinfunction "GND_H25") (pintype "power_in"))
      (node (ref "U$2") (pin "H27") (pinfunction "GND_H27") (pintype "power_in"))
      (node (ref "U$2") (pin "H6") (pinfunction "GND_H6") (pintype "power_in"))
      (node (ref "U$2") (pin "H9") (pinfunction "GND_H9") (pintype "power_in"))
      (node (ref "U$4") (pin "2") (pinfunction "GND_2") (pintype "power_in"))
      (node (ref "U$4") (pin "EP") (pinfunction "EP_EP") (pintype "power_in"))
      (node (ref "U1") (pin "5") (pinfunction "ANODE_5") (pintype "input"))
      (node (ref "U2") (pin "5") (pinfunction "ANODE_5") (pintype "input"))
      (node (ref "U4") (pin "1") (pinfunction "~{1OE}_1") (pintype "input"))
      (node (ref "U4") (pin "10") (pinfunction "GND_10") (pintype "passive"))
      (node (ref "U4") (pin "11") (pinfunction "GND_11") (pintype "passive"))
      (node (ref "U4") (pin "16") (pinfunction "~{2OE}_16") (pintype "input"))
      (node (ref "U4") (pin "4") (pinfunction "1DIR_4") (pintype "input"))
      (node (ref "U4") (pin "9") (pinfunction "2A2_9") (pintype "output"))
      (node (ref "U5") (pin "6") (pinfunction "DIR4_6") (pintype "input"))
      (node (ref "U5") (pin "7") (pinfunction "~{OE}_7") (pintype "input"))
      (node (ref "U5") (pin "8") (pinfunction "GND_8") (pintype "passive"))
      (node (ref "U6") (pin "15") (pinfunction "DIR1_15") (pintype "input"))
      (node (ref "U6") (pin "5") (pinfunction "DIR3_5") (pintype "input"))
      (node (ref "U6") (pin "6") (pinfunction "DIR4_6") (pintype "input"))
      (node (ref "U6") (pin "7") (pinfunction "~{OE}_7") (pintype "input"))
      (node (ref "U6") (pin "8") (pinfunction "GND_8") (pintype "passive"))
      (node (ref "UEP") (pin "1") (pinfunction "A0_1") (pintype "input"))
      (node (ref "UEP") (pin "2") (pinfunction "A1_2") (pintype "input"))
      (node (ref "UEP") (pin "3") (pinfunction "A2_3") (pintype "input"))
      (node (ref "UEP") (pin "4") (pinfunction "GND_4") (pintype "passive"))
      (node (ref "UEP") (pin "EP") (pinfunction "EP_EP") (pintype "passive"))
      (node (ref "UNE") (pin "4") (pinfunction "VSS_4") (pintype "power_in"))
      (node (ref "UNE") (pin "EP") (pinfunction "EP_EP") (pintype "passive"))
      (node (ref "UNN") (pin "4") (pinfunction "VSS_4") (pintype "power_in"))
      (node (ref "UNN") (pin "EP") (pinfunction "EP_EP") (pintype "passive"))
      (node (ref "UNW") (pin "4") (pinfunction "VSS_4") (pintype "power_in"))
      (node (ref "UNW") (pin "EP") (pinfunction "EP_EP") (pintype "passive"))
      (node (ref "USE") (pin "4") (pinfunction "VSS_4") (pintype "power_in"))
      (node (ref "USE") (pin "EP") (pinfunction "EP_EP") (pintype "passive"))
      (node (ref "USS") (pin "4") (pinfunction "VSS_4") (pintype "power_in"))
      (node (ref "USS") (pin "EP") (pinfunction "EP_EP") (pintype "passive"))
      (node (ref "USW") (pin "4") (pinfunction "VSS_4") (pintype "power_in"))
      (node (ref "USW") (pin "EP") (pinfunction "EP_EP") (pintype "passive"))
      (node (ref "X-NORTH") (pin "102") (pinfunction "102_102") (pintype "bidirectional"))
      (node (ref "X-NORTH") (pin "108") (pinfunction "108_108") (pintype "bidirectional"))
      (node (ref "X-NORTH") (pin "114") (pinfunction "114_114") (pintype "bidirectional"))
      (node (ref "X-NORTH") (pin "12") (pinfunction "12_12") (pintype "bidirectional"))
      (node (ref "X-NORTH") (pin "120") (pinfunction "120_120") (pintype "bidirectional"))
      (node (ref "X-NORTH") (pin "126") (pinfunction "126_126") (pintype "bidirectional"))
      (node (ref "X-NORTH") (pin "132") (pinfunction "132_132") (pintype "bidirectional"))
      (node (ref "X-NORTH") (pin "138") (pinfunction "138_138") (pintype "bidirectional"))
      (node (ref "X-NORTH") (pin "139") (pinfunction "139_139") (pintype "bidirectional"))
      (node (ref "X-NORTH") (pin "18") (pinfunction "18_18") (pintype "bidirectional"))
      (node (ref "X-NORTH") (pin "24") (pinfunction "24_24") (pintype "bidirectional"))
      (node (ref "X-NORTH") (pin "30") (pinfunction "30_30") (pintype "bidirectional"))
      (node (ref "X-NORTH") (pin "36") (pinfunction "36_36") (pintype "bidirectional"))
      (node (ref "X-NORTH") (pin "42") (pinfunction "42_42") (pintype "bidirectional"))
      (node (ref "X-NORTH") (pin "48") (pinfunction "48_48") (pintype "bidirectional"))
      (node (ref "X-NORTH") (pin "54") (pinfunction "54_54") (pintype "bidirectional"))
      (node (ref "X-NORTH") (pin "60") (pinfunction "60_60") (pintype "bidirectional"))
      (node (ref "X-NORTH") (pin "66") (pinfunction "66_66") (pintype "bidirectional"))
      (node (ref "X-NORTH") (pin "72") (pinfunction "72_72") (pintype "bidirectional"))
      (node (ref "X-NORTH") (pin "78") (pinfunction "78_78") (pintype "bidirectional"))
      (node (ref "X-NORTH") (pin "84") (pinfunction "84_84") (pintype "bidirectional"))
      (node (ref "X-NORTH") (pin "90") (pinfunction "90_90") (pintype "bidirectional"))
      (node (ref "X-NORTH") (pin "96") (pinfunction "96_96") (pintype "bidirectional"))
      (node (ref "X-SOUTH") (pin "102") (pinfunction "102_102") (pintype "bidirectional"))
      (node (ref "X-SOUTH") (pin "108") (pinfunction "108_108") (pintype "bidirectional"))
      (node (ref "X-SOUTH") (pin "114") (pinfunction "114_114") (pintype "bidirectional"))
      (node (ref "X-SOUTH") (pin "12") (pinfunction "12_12") (pintype "bidirectional"))
      (node (ref "X-SOUTH") (pin "120") (pinfunction "120_120") (pintype "bidirectional"))
      (node (ref "X-SOUTH") (pin "126") (pinfunction "126_126") (pintype "bidirectional"))
      (node (ref "X-SOUTH") (pin "132") (pinfunction "132_132") (pintype "bidirectional"))
      (node (ref "X-SOUTH") (pin "138") (pinfunction "138_138") (pintype "bidirectional"))
      (node (ref "X-SOUTH") (pin "139") (pinfunction "139_139") (pintype "bidirectional"))
      (node (ref "X-SOUTH") (pin "18") (pinfunction "18_18") (pintype "bidirectional"))
      (node (ref "X-SOUTH") (pin "24") (pinfunction "24_24") (pintype "bidirectional"))
      (node (ref "X-SOUTH") (pin "30") (pinfunction "30_30") (pintype "bidirectional"))
      (node (ref "X-SOUTH") (pin "36") (pinfunction "36_36") (pintype "bidirectional"))
      (node (ref "X-SOUTH") (pin "42") (pinfunction "42_42") (pintype "bidirectional"))
      (node (ref "X-SOUTH") (pin "48") (pinfunction "48_48") (pintype "bidirectional"))
      (node (ref "X-SOUTH") (pin "54") (pinfunction "54_54") (pintype "bidirectional"))
      (node (ref "X-SOUTH") (pin "60") (pinfunction "60_60") (pintype "bidirectional"))
      (node (ref "X-SOUTH") (pin "66") (pinfunction "66_66") (pintype "bidirectional"))
      (node (ref "X-SOUTH") (pin "72") (pinfunction "72_72") (pintype "bidirectional"))
      (node (ref "X-SOUTH") (pin "78") (pinfunction "78_78") (pintype "bidirectional"))
      (node (ref "X-SOUTH") (pin "84") (pinfunction "84_84") (pintype "bidirectional"))
      (node (ref "X-SOUTH") (pin "90") (pinfunction "90_90") (pintype "bidirectional"))
      (node (ref "X-SOUTH") (pin "96") (pinfunction "96_96") (pintype "bidirectional"))
    )
    (net (code "4") (name "N$38") (class "Default")
      (node (ref "U$2") (pin "F4") (pinfunction "DIO1_F4") (pintype "output"))
    )
    (net (code "5") (name "N$39") (class "Default")
      (node (ref "U$2") (pin "E4") (pinfunction "DIO2_E4") (pintype "output"))
    )
    (net (code "6") (name "N$40") (class "Default")
      (node (ref "U$2") (pin "H4") (pinfunction "DIO3_H4") (pintype "output"))
    )
    (net (code "7") (name "N$41") (class "Default")
      (node (ref "U$2") (pin "G3") (pinfunction "DIO4_G3") (pintype "output"))
    )
    (net (code "8") (name "N$42") (class "Default")
      (node (ref "U$2") (pin "A2") (pinfunction "TANA_A2") (pintype "output"))
    )
    (net (code "9") (name "N00_N") (class "Default")
      (node (ref "R25") (pin "2") (pinfunction "2_2") (pintype "passive"))
      (node (ref "U$2") (pin "E6") (pinfunction "LVDS_CLK_P_E6") (pintype "input"))
      (node (ref "X-NORTH") (pin "16") (pinfunction "16_16") (pintype "bidirectional"))
    )
    (net (code "10") (name "N00_P") (class "Default")
      (node (ref "R25") (pin "1") (pinfunction "1_1") (pintype "passive"))
      (node (ref "U$2") (pin "E5") (pinfunction "LVDS_CLK_N_E5") (pintype "input"))
      (node (ref "X-NORTH") (pin "14") (pinfunction "14_14") (pintype "bidirectional"))
    )
    (net (code "11") (name "N01_N") (class "Default")
      (node (ref "U$2") (pin "G7") (pinfunction "OUTCLK_P_G7") (pintype "output"))
      (node (ref "X-NORTH") (pin "17") (pinfunction "17_17") (pintype "bidirectional"))
    )
    (net (code "12") (name "N01_P") (class "Default")
      (node (ref "U$2") (pin "G6") (pinfunction "OUTCLK_N_G6") (pintype "output"))
      (node (ref "X-NORTH") (pin "15") (pinfunction "15_15") (pintype "bidirectional"))
    )
    (net (code "13") (name "N02_N") (class "Default")
      (node (ref "U$2") (pin "F7") (pinfunction "OUT33_P_F7") (pintype "output"))
      (node (ref "X-NORTH") (pin "22") (pinfunction "22_22") (pintype "bidirectional"))
    )
    (net (code "14") (name "N02_P") (class "Default")
      (node (ref "U$2") (pin "F6") (pinfunction "OUT33_N_F6") (pintype "output"))
      (node (ref "X-NORTH") (pin "20") (pinfunction "20_20") (pintype "bidirectional"))
    )
    (net (code "15") (name "N03_N") (class "Default")
      (node (ref "X-NORTH") (pin "23") (pinfunction "23_23") (pintype "bidirectional"))
    )
    (net (code "16") (name "N03_P") (class "Default")
      (node (ref "X-NORTH") (pin "21") (pinfunction "21_21") (pintype "bidirectional"))
    )
    (net (code "17") (name "N04_N") (class "Default")
      (node (ref "U$2") (pin "E8") (pinfunction "OUT35_P_E8") (pintype "output"))
      (node (ref "X-NORTH") (pin "28") (pinfunction "28_28") (pintype "bidirectional"))
    )
    (net (code "18") (name "N04_P") (class "Default")
      (node (ref "U$2") (pin "E7") (pinfunction "OUT35_N_E7") (pintype "output"))
      (node (ref "X-NORTH") (pin "26") (pinfunction "26_26") (pintype "bidirectional"))
    )
    (net (code "19") (name "N05_N") (class "Default")
      (node (ref "U$2") (pin "H8") (pinfunction "OUT34_P_H8") (pintype "output"))
      (node (ref "X-NORTH") (pin "29") (pinfunction "29_29") (pintype "bidirectional"))
    )
    (net (code "20") (name "N05_P") (class "Default")
      (node (ref "U$2") (pin "H7") (pinfunction "OUT34_N_H7") (pintype "output"))
      (node (ref "X-NORTH") (pin "27") (pinfunction "27_27") (pintype "bidirectional"))
    )
    (net (code "21") (name "N06_N") (class "Default")
      (node (ref "U$2") (pin "F9") (pinfunction "OUT37_P_F9") (pintype "output"))
      (node (ref "X-NORTH") (pin "34") (pinfunction "34_34") (pintype "bidirectional"))
    )
    (net (code "22") (name "N06_P") (class "Default")
      (node (ref "U$2") (pin "F8") (pinfunction "OUT37_N_F8") (pintype "output"))
      (node (ref "X-NORTH") (pin "32") (pinfunction "32_32") (pintype "bidirectional"))
    )
    (net (code "23") (name "N07_N") (class "Default")
      (node (ref "U$2") (pin "G9") (pinfunction "OUT36_P_G9") (pintype "output"))
      (node (ref "X-NORTH") (pin "35") (pinfunction "35_35") (pintype "bidirectional"))
    )
    (net (code "24") (name "N07_P") (class "Default")
      (node (ref "U$2") (pin "G8") (pinfunction "OUT36_N_G8") (pintype "output"))
      (node (ref "X-NORTH") (pin "33") (pinfunction "33_33") (pintype "bidirectional"))
    )
    (net (code "25") (name "N08_N") (class "Default")
      (node (ref "U$2") (pin "E10") (pinfunction "OUT38_P_E10") (pintype "output"))
      (node (ref "X-NORTH") (pin "40") (pinfunction "40_40") (pintype "bidirectional"))
    )
    (net (code "26") (name "N08_P") (class "Default")
      (node (ref "U$2") (pin "E9") (pinfunction "OUT38_N_E9") (pintype "output"))
      (node (ref "X-NORTH") (pin "38") (pinfunction "38_38") (pintype "bidirectional"))
    )
    (net (code "27") (name "N09_N") (class "Default")
      (node (ref "U$2") (pin "G11") (pinfunction "OUT39_P_G11") (pintype "output"))
      (node (ref "X-NORTH") (pin "41") (pinfunction "41_41") (pintype "bidirectional"))
    )
    (net (code "28") (name "N09_P") (class "Default")
      (node (ref "U$2") (pin "G10") (pinfunction "OUT39_N_G10") (pintype "output"))
      (node (ref "X-NORTH") (pin "39") (pinfunction "39_39") (pintype "bidirectional"))
    )
    (net (code "29") (name "N10_N") (class "Default")
      (node (ref "U$2") (pin "F11") (pinfunction "OUT40_P_F11") (pintype "output"))
      (node (ref "X-NORTH") (pin "46") (pinfunction "46_46") (pintype "bidirectional"))
    )
    (net (code "30") (name "N10_P") (class "Default")
      (node (ref "U$2") (pin "F10") (pinfunction "OUT40_N_F10") (pintype "output"))
      (node (ref "X-NORTH") (pin "44") (pinfunction "44_44") (pintype "bidirectional"))
    )
    (net (code "31") (name "N11_N") (class "Default")
      (node (ref "U$2") (pin "H12") (pinfunction "OUT41_P_H12") (pintype "output"))
      (node (ref "X-NORTH") (pin "47") (pinfunction "47_47") (pintype "bidirectional"))
    )
    (net (code "32") (name "N11_P") (class "Default")
      (node (ref "U$2") (pin "H11") (pinfunction "OUT41_N_H11") (pintype "output"))
      (node (ref "X-NORTH") (pin "45") (pinfunction "45_45") (pintype "bidirectional"))
    )
    (net (code "33") (name "N12_N") (class "Default")
      (node (ref "U$2") (pin "E12") (pinfunction "OUT42_P_E12") (pintype "output"))
      (node (ref "X-NORTH") (pin "52") (pinfunction "52_52") (pintype "bidirectional"))
    )
    (net (code "34") (name "N12_P") (class "Default")
      (node (ref "U$2") (pin "E11") (pinfunction "OUT42_N_E11") (pintype "output"))
      (node (ref "X-NORTH") (pin "50") (pinfunction "50_50") (pintype "bidirectional"))
    )
    (net (code "35") (name "N13_N") (class "Default")
      (node (ref "U$2") (pin "G13") (pinfunction "OUT43_P_G13") (pintype "output"))
      (node (ref "X-NORTH") (pin "53") (pinfunction "53_53") (pintype "bidirectional"))
    )
    (net (code "36") (name "N13_P") (class "Default")
      (node (ref "U$2") (pin "G12") (pinfunction "OUT43_N_G12") (pintype "output"))
      (node (ref "X-NORTH") (pin "51") (pinfunction "51_51") (pintype "bidirectional"))
    )
    (net (code "37") (name "N14_N") (class "Default")
      (node (ref "U$2") (pin "F13") (pinfunction "OUT44_P_F13") (pintype "output"))
      (node (ref "X-NORTH") (pin "58") (pinfunction "58_58") (pintype "bidirectional"))
    )
    (net (code "38") (name "N14_P") (class "Default")
      (node (ref "U$2") (pin "F12") (pinfunction "OUT44_N_F12") (pintype "output"))
      (node (ref "X-NORTH") (pin "56") (pinfunction "56_56") (pintype "bidirectional"))
    )
    (net (code "39") (name "N15_N") (class "Default")
      (node (ref "U$2") (pin "H14") (pinfunction "OUT45_P_H14") (pintype "output"))
      (node (ref "X-NORTH") (pin "59") (pinfunction "59_59") (pintype "bidirectional"))
    )
    (net (code "40") (name "N15_P") (class "Default")
      (node (ref "U$2") (pin "H13") (pinfunction "OUT45_N_H13") (pintype "output"))
      (node (ref "X-NORTH") (pin "57") (pinfunction "57_57") (pintype "bidirectional"))
    )
    (net (code "41") (name "N16_N") (class "Default")
      (node (ref "U$2") (pin "E14") (pinfunction "OUT46_P_E14") (pintype "output"))
      (node (ref "X-NORTH") (pin "64") (pinfunction "64_64") (pintype "bidirectional"))
    )
    (net (code "42") (name "N16_P") (class "Default")
      (node (ref "U$2") (pin "E13") (pinfunction "OUT46_N_E13") (pintype "output"))
      (node (ref "X-NORTH") (pin "62") (pinfunction "62_62") (pintype "bidirectional"))
    )
    (net (code "43") (name "N17_N") (class "Default")
      (node (ref "U$2") (pin "G15") (pinfunction "OUT47_P_G15") (pintype "output"))
      (node (ref "X-NORTH") (pin "65") (pinfunction "65_65") (pintype "bidirectional"))
    )
    (net (code "44") (name "N17_P") (class "Default")
      (node (ref "U$2") (pin "G14") (pinfunction "OUT47_N_G14") (pintype "output"))
      (node (ref "X-NORTH") (pin "63") (pinfunction "63_63") (pintype "bidirectional"))
    )
    (net (code "45") (name "N18_N") (class "Default")
      (node (ref "U$2") (pin "F15") (pinfunction "OUT48_P_F15") (pintype "output"))
      (node (ref "X-NORTH") (pin "70") (pinfunction "70_70") (pintype "bidirectional"))
    )
    (net (code "46") (name "N18_P") (class "Default")
      (node (ref "U$2") (pin "F14") (pinfunction "OUT48_N_F14") (pintype "output"))
      (node (ref "X-NORTH") (pin "68") (pinfunction "68_68") (pintype "bidirectional"))
    )
    (net (code "47") (name "N19_N") (class "Default")
      (node (ref "U$2") (pin "G17") (pinfunction "OUT50_P_G17") (pintype "output"))
      (node (ref "X-NORTH") (pin "71") (pinfunction "71_71") (pintype "bidirectional"))
    )
    (net (code "48") (name "N19_P") (class "Default")
      (node (ref "U$2") (pin "G16") (pinfunction "OUT50_N_G16") (pintype "output"))
      (node (ref "X-NORTH") (pin "69") (pinfunction "69_69") (pintype "bidirectional"))
    )
    (net (code "49") (name "N20_N") (class "Default")
      (node (ref "U$2") (pin "F17") (pinfunction "OUT49_P_F17") (pintype "output"))
      (node (ref "X-NORTH") (pin "76") (pinfunction "76_76") (pintype "bidirectional"))
    )
    (net (code "50") (name "N20_P") (class "Default")
      (node (ref "U$2") (pin "F16") (pinfunction "OUT49_N_F16") (pintype "output"))
      (node (ref "X-NORTH") (pin "74") (pinfunction "74_74") (pintype "bidirectional"))
    )
    (net (code "51") (name "N21_N") (class "Default")
      (node (ref "U$2") (pin "H18") (pinfunction "OUT52_P_H18") (pintype "output"))
      (node (ref "X-NORTH") (pin "77") (pinfunction "77_77") (pintype "bidirectional"))
    )
    (net (code "52") (name "N21_P") (class "Default")
      (node (ref "U$2") (pin "H17") (pinfunction "OUT52_N_H17") (pintype "output"))
      (node (ref "X-NORTH") (pin "75") (pinfunction "75_75") (pintype "bidirectional"))
    )
    (net (code "53") (name "N22_N") (class "Default")
      (node (ref "U$2") (pin "E18") (pinfunction "OUT51_P_E18") (pintype "output"))
      (node (ref "X-NORTH") (pin "82") (pinfunction "82_82") (pintype "bidirectional"))
    )
    (net (code "54") (name "N22_P") (class "Default")
      (node (ref "U$2") (pin "E17") (pinfunction "OUT51_N_E17") (pintype "output"))
      (node (ref "X-NORTH") (pin "80") (pinfunction "80_80") (pintype "bidirectional"))
    )
    (net (code "55") (name "N23_N") (class "Default")
      (node (ref "U$2") (pin "G19") (pinfunction "OUT54_P_G19") (pintype "output"))
      (node (ref "X-NORTH") (pin "83") (pinfunction "83_83") (pintype "bidirectional"))
    )
    (net (code "56") (name "N23_P") (class "Default")
      (node (ref "U$2") (pin "G18") (pinfunction "OUT54_N_G18") (pintype "output"))
      (node (ref "X-NORTH") (pin "81") (pinfunction "81_81") (pintype "bidirectional"))
    )
    (net (code "57") (name "N24_N") (class "Default")
      (node (ref "U$2") (pin "F19") (pinfunction "OUT53_P_F19") (pintype "output"))
      (node (ref "X-NORTH") (pin "88") (pinfunction "88_88") (pintype "bidirectional"))
    )
    (net (code "58") (name "N24_P") (class "Default")
      (node (ref "U$2") (pin "F18") (pinfunction "OUT53_N_F18") (pintype "output"))
      (node (ref "X-NORTH") (pin "86") (pinfunction "86_86") (pintype "bidirectional"))
    )
    (net (code "59") (name "N25_N") (class "Default")
      (node (ref "U$2") (pin "H20") (pinfunction "OUT56_P_H20") (pintype "output"))
      (node (ref "X-NORTH") (pin "89") (pinfunction "89_89") (pintype "bidirectional"))
    )
    (net (code "60") (name "N25_P") (class "Default")
      (node (ref "U$2") (pin "H19") (pinfunction "OUT56_N_H19") (pintype "output"))
      (node (ref "X-NORTH") (pin "87") (pinfunction "87_87") (pintype "bidirectional"))
    )
    (net (code "61") (name "N26_N") (class "Default")
      (node (ref "U$2") (pin "E20") (pinfunction "OUT55_P_E20") (pintype "output"))
      (node (ref "X-NORTH") (pin "94") (pinfunction "94_94") (pintype "bidirectional"))
    )
    (net (code "62") (name "N26_P") (class "Default")
      (node (ref "U$2") (pin "E19") (pinfunction "OUT55_N_E19") (pintype "output"))
      (node (ref "X-NORTH") (pin "92") (pinfunction "92_92") (pintype "bidirectional"))
    )
    (net (code "63") (name "N27_N") (class "Default")
      (node (ref "U$2") (pin "G21") (pinfunction "OUT58_P_G21") (pintype "output"))
      (node (ref "X-NORTH") (pin "95") (pinfunction "95_95") (pintype "bidirectional"))
    )
    (net (code "64") (name "N27_P") (class "Default")
      (node (ref "U$2") (pin "G20") (pinfunction "OUT58_N_G20") (pintype "output"))
      (node (ref "X-NORTH") (pin "93") (pinfunction "93_93") (pintype "bidirectional"))
    )
    (net (code "65") (name "N28_N") (class "Default")
      (node (ref "U$2") (pin "F21") (pinfunction "OUT57_P_F21") (pintype "output"))
      (node (ref "X-NORTH") (pin "100") (pinfunction "100_100") (pintype "bidirectional"))
    )
    (net (code "66") (name "N28_P") (class "Default")
      (node (ref "U$2") (pin "F20") (pinfunction "OUT57_N_F20") (pintype "output"))
      (node (ref "X-NORTH") (pin "98") (pinfunction "98_98") (pintype "bidirectional"))
    )
    (net (code "67") (name "N29_N") (class "Default")
      (node (ref "U$2") (pin "G23") (pinfunction "OUT61_P_G23") (pintype "output"))
      (node (ref "X-NORTH") (pin "101") (pinfunction "101_101") (pintype "bidirectional"))
    )
    (net (code "68") (name "N29_P") (class "Default")
      (node (ref "U$2") (pin "G22") (pinfunction "OUT61_N_G22") (pintype "output"))
      (node (ref "X-NORTH") (pin "99") (pinfunction "99_99") (pintype "bidirectional"))
    )
    (net (code "69") (name "N30_N") (class "Default")
      (node (ref "U$2") (pin "E22") (pinfunction "OUT59_P_E22") (pintype "output"))
      (node (ref "X-NORTH") (pin "106") (pinfunction "106_106") (pintype "bidirectional"))
    )
    (net (code "70") (name "N30_P") (class "Default")
      (node (ref "U$2") (pin "E21") (pinfunction "OUT59_N_E21") (pintype "output"))
      (node (ref "X-NORTH") (pin "104") (pinfunction "104_104") (pintype "bidirectional"))
    )
    (net (code "71") (name "N31_N") (class "Default")
      (node (ref "U$2") (pin "H24") (pinfunction "OUT63_P_H24") (pintype "output"))
      (node (ref "X-NORTH") (pin "107") (pinfunction "107_107") (pintype "bidirectional"))
    )
    (net (code "72") (name "N31_P") (class "Default")
      (node (ref "U$2") (pin "H23") (pinfunction "OUT63_N_H23") (pintype "output"))
      (node (ref "X-NORTH") (pin "105") (pinfunction "105_105") (pintype "bidirectional"))
    )
    (net (code "73") (name "N32_N") (class "Default")
      (node (ref "U$2") (pin "F23") (pinfunction "OUT60_P_F23") (pintype "output"))
      (node (ref "X-NORTH") (pin "112") (pinfunction "112_112") (pintype "bidirectional"))
    )
    (net (code "74") (name "N32_P") (class "Default")
      (node (ref "U$2") (pin "F22") (pinfunction "OUT60_N_F22") (pintype "output"))
      (node (ref "X-NORTH") (pin "110") (pinfunction "110_110") (pintype "bidirectional"))
    )
    (net (code "75") (name "N33_N") (class "Default")
      (node (ref "U$2") (pin "G25") (pinfunction "OUT64_P_G25") (pintype "output"))
      (node (ref "X-NORTH") (pin "113") (pinfunction "113_113") (pintype "bidirectional"))
    )
    (net (code "76") (name "N33_P") (class "Default")
      (node (ref "U$2") (pin "G24") (pinfunction "OUT64_N_G24") (pintype "output"))
      (node (ref "X-NORTH") (pin "111") (pinfunction "111_111") (pintype "bidirectional"))
    )
    (net (code "77") (name "N34_N") (class "Default")
      (node (ref "U$2") (pin "E24") (pinfunction "OUT62_P_E24") (pintype "output"))
      (node (ref "X-NORTH") (pin "118") (pinfunction "118_118") (pintype "bidirectional"))
    )
    (net (code "78") (name "N34_P") (class "Default")
      (node (ref "U$2") (pin "E23") (pinfunction "OUT62_N_E23") (pintype "output"))
      (node (ref "X-NORTH") (pin "116") (pinfunction "116_116") (pintype "bidirectional"))
    )
    (net (code "79") (name "N35_N") (class "Default")
      (node (ref "U6") (pin "4") (pinfunction "A4_4") (pintype "bidirectional"))
      (node (ref "X-NORTH") (pin "119") (pinfunction "119_119") (pintype "bidirectional"))
    )
    (net (code "80") (name "N35_P") (class "Default")
      (node (ref "U6") (pin "3") (pinfunction "A3_3") (pintype "bidirectional"))
      (node (ref "X-NORTH") (pin "117") (pinfunction "117_117") (pintype "bidirectional"))
    )
    (net (code "81") (name "N36_N") (class "Default")
      (node (ref "X-NORTH") (pin "124") (pinfunction "124_124") (pintype "bidirectional"))
    )
    (net (code "82") (name "N36_P") (class "Default")
      (node (ref "X-NORTH") (pin "122") (pinfunction "122_122") (pintype "bidirectional"))
    )
    (net (code "83") (name "N37_N") (class "Default")
      (node (ref "U5") (pin "3") (pinfunction "A3_3") (pintype "bidirectional"))
      (node (ref "X-NORTH") (pin "125") (pinfunction "125_125") (pintype "bidirectional"))
    )
    (net (code "84") (name "N37_P") (class "Default")
      (node (ref "U5") (pin "4") (pinfunction "A4_4") (pintype "bidirectional"))
      (node (ref "X-NORTH") (pin "123") (pinfunction "123_123") (pintype "bidirectional"))
    )
    (net (code "85") (name "N38_N") (class "Default")
      (node (ref "U6") (pin "2") (pinfunction "A2_2") (pintype "bidirectional"))
      (node (ref "X-NORTH") (pin "130") (pinfunction "130_130") (pintype "bidirectional"))
    )
    (net (code "86") (name "N38_P") (class "Default")
      (node (ref "U6") (pin "1") (pinfunction "A1_1") (pintype "bidirectional"))
      (node (ref "X-NORTH") (pin "128") (pinfunction "128_128") (pintype "bidirectional"))
    )
    (net (code "87") (name "N39_N") (class "Default")
      (node (ref "U5") (pin "1") (pinfunction "A1_1") (pintype "bidirectional"))
      (node (ref "X-NORTH") (pin "131") (pinfunction "131_131") (pintype "bidirectional"))
    )
    (net (code "88") (name "N39_P") (class "Default")
      (node (ref "U5") (pin "2") (pinfunction "A2_2") (pintype "bidirectional"))
      (node (ref "X-NORTH") (pin "129") (pinfunction "129_129") (pintype "bidirectional"))
    )
    (net (code "89") (name "N_CHK_V") (class "Default")
      (node (ref "C2") (pin "1") (pinfunction "1_1") (pintype "passive"))
      (node (ref "C3") (pin "1") (pinfunction "1_1") (pintype "passive"))
      (node (ref "C4") (pin "1") (pinfunction "1_1") (pintype "passive"))
      (node (ref "R19") (pin "1") (pinfunction "1_1") (pintype "passive"))
      (node (ref "TP1") (pin "TP") (pinfunction "TP_TP") (pintype "input"))
      (node (ref "UNE") (pin "8") (pinfunction "VDD_8") (pintype "power_in"))
      (node (ref "UNN") (pin "8") (pinfunction "VDD_8") (pintype "power_in"))
      (node (ref "UNW") (pin "8") (pinfunction "VDD_8") (pintype "power_in"))
      (node (ref "X-NORTH") (pin "10") (pinfunction "10_10") (pintype "bidirectional"))
      (node (ref "X-NORTH") (pin "8") (pinfunction "8_8") (pintype "bidirectional"))
    )
    (net (code "90") (name "N_I2C_V") (class "Default")
      (node (ref "C1") (pin "1") (pinfunction "1_1") (pintype "passive"))
      (node (ref "R1X") (pin "1") (pinfunction "1_1") (pintype "passive"))
      (node (ref "UEP") (pin "8") (pinfunction "VCC_8") (pintype "power_in"))
      (node (ref "X-NORTH") (pin "135") (pinfunction "135_135") (pintype "bidirectional"))
      (node (ref "X-NORTH") (pin "137") (pinfunction "137_137") (pintype "bidirectional"))
    )
    (net (code "91") (name "N_REF") (class "Default")
      (node (ref "R19") (pin "2") (pinfunction "2_2") (pintype "passive"))
      (node (ref "TP2") (pin "TP") (pinfunction "TP_TP") (pintype "input"))
      (node (ref "U1") (pin "3") (pinfunction "CATHODE_3") (pintype "output"))
      (node (ref "U1") (pin "4") (pinfunction "REF_4") (pintype "input"))
      (node (ref "UNE") (pin "2") (pinfunction "VINA-_2") (pintype "input"))
      (node (ref "UNE") (pin "5") (pinfunction "VINB+_5") (pintype "input"))
      (node (ref "UNN") (pin "2") (pinfunction "VINA-_2") (pintype "input"))
      (node (ref "UNN") (pin "5") (pinfunction "VINB+_5") (pintype "input"))
      (node (ref "UNW") (pin "2") (pinfunction "VINA-_2") (pintype "input"))
      (node (ref "UNW") (pin "5") (pinfunction "VINB+_5") (pintype "input"))
    )
    (net (code "92") (name "N_SCK") (class "Default")
      (node (ref "U4") (pin "15") (pinfunction "1B1_15") (pintype "output"))
      (node (ref "X-NORTH") (pin "144") (pinfunction "144_144") (pintype "bidirectional"))
    )
    (net (code "93") (name "N_SCL") (class "Default")
      (node (ref "UEP") (pin "6") (pinfunction "SCL_6") (pintype "input"))
      (node (ref "X-NORTH") (pin "143") (pinfunction "143_143") (pintype "bidirectional"))
    )
    (net (code "94") (name "N_SDA") (class "Default")
      (node (ref "UEP") (pin "5") (pinfunction "SDA_5") (pintype "bidirectional"))
      (node (ref "X-NORTH") (pin "141") (pinfunction "141_141") (pintype "bidirectional"))
    )
    (net (code "95") (name "N_SDI") (class "Default")
      (node (ref "U4") (pin "13") (pinfunction "2B1_13") (pintype "output"))
      (node (ref "X-NORTH") (pin "140") (pinfunction "140_140") (pintype "bidirectional"))
    )
    (net (code "96") (name "N_SDO") (class "Default")
      (node (ref "U4") (pin "14") (pinfunction "1B2_14") (pintype "output"))
      (node (ref "X-NORTH") (pin "142") (pinfunction "142_142") (pintype "bidirectional"))
    )
    (net (code "97") (name "N_SPI_V") (class "Default")
      (node (ref "C71") (pin "1") (pinfunction "1_1") (pintype "passive"))
      (node (ref "U4") (pin "2") (pinfunction "VCCB_2") (pintype "power_in"))
      (node (ref "X-NORTH") (pin "134") (pinfunction "134_134") (pintype "bidirectional"))
      (node (ref "X-NORTH") (pin "136") (pinfunction "136_136") (pintype "bidirectional"))
    )
    (net (code "98") (name "N_VE") (class "Default")
      (node (ref "C50") (pin "1") (pinfunction "1_1") (pintype "passive"))
      (node (ref "C51") (pin "1") (pinfunction "1_1") (pintype "passive"))
      (node (ref "C52") (pin "1") (pinfunction "1_1") (pintype "passive"))
      (node (ref "C53") (pin "1") (pinfunction "1_1") (pintype "passive"))
      (node (ref "C54") (pin "1") (pinfunction "1_1") (pintype "passive"))
      (node (ref "C55") (pin "1") (pinfunction "1_1") (pintype "passive"))
      (node (ref "C56") (pin "1") (pinfunction "1_1") (pintype "passive"))
      (node (ref "C67") (pin "1") (pinfunction "1_1") (pintype "passive"))
      (node (ref "C69") (pin "1") (pinfunction "1_1") (pintype "passive"))
      (node (ref "C75") (pin "1") (pinfunction "1_1") (pintype "passive"))
      (node (ref "C76") (pin "1") (pinfunction "1_1") (pintype "passive"))
      (node (ref "C77") (pin "1") (pinfunction "1_1") (pintype "passive"))
      (node (ref "C84") (pin "1") (pinfunction "1_1") (pintype "passive"))
      (node (ref "C85") (pin "1") (pinfunction "1_1") (pintype "passive"))
      (node (ref "C86") (pin "1") (pinfunction "1_1") (pintype "passive"))
      (node (ref "TP7") (pin "TP") (pinfunction "TP_TP") (pintype "input"))
      (node (ref "U$2") (pin "C26") (pinfunction "VDD33_C26") (pintype "power_in"))
      (node (ref "U$2") (pin "C27") (pinfunction "VDD33_C27") (pintype "power_in"))
      (node (ref "U$2") (pin "D26") (pinfunction "VDD33_D26") (pintype "power_in"))
      (node (ref "U$2") (pin "D3") (pinfunction "VDD33_D3") (pintype "power_in"))
      (node (ref "U$2") (pin "E26") (pinfunction "VDD33_E26") (pintype "power_in"))
      (node (ref "U$2") (pin "F26") (pinfunction "VDD33_F26") (pintype "power_in"))
      (node (ref "U$2") (pin "F5") (pinfunction "VDD33_F5") (pintype "power_in"))
      (node (ref "U4") (pin "3") (pinfunction "VCCA_3") (pintype "power_in"))
      (node (ref "U4") (pin "5") (pinfunction "2DIR_5") (pintype "input"))
      (node (ref "U5") (pin "13") (pinfunction "VCCB_13") (pintype "power_in"))
      (node (ref "U6") (pin "13") (pinfunction "VCCB_13") (pintype "power_in"))
      (node (ref "X-NORTH") (pin "103") (pinfunction "103_103") (pintype "bidirectional"))
      (node (ref "X-NORTH") (pin "109") (pinfunction "109_109") (pintype "bidirectional"))
      (node (ref "X-NORTH") (pin "115") (pinfunction "115_115") (pintype "bidirectional"))
      (node (ref "X-NORTH") (pin "121") (pinfunction "121_121") (pintype "bidirectional"))
      (node (ref "X-NORTH") (pin "127") (pinfunction "127_127") (pintype "bidirectional"))
      (node (ref "X-NORTH") (pin "133") (pinfunction "133_133") (pintype "bidirectional"))
    )
    (net (code "99") (name "N_VE_CV") (class "Default")
      (node (ref "C10") (pin "1") (pinfunction "1_1") (pintype "passive"))
      (node (ref "R7") (pin "1") (pinfunction "1_1") (pintype "passive"))
      (node (ref "X-NORTH") (pin "6") (pinfunction "6_6") (pintype "bidirectional"))
    )
    (net (code "100") (name "N_VE_OV") (class "Default")
      (node (ref "UNE") (pin "7") (pinfunction "OUTB_7") (pintype "output"))
      (node (ref "X-NORTH") (pin "5") (pinfunction "5_5") (pintype "bidirectional"))
    )
    (net (code "101") (name "N_VE_UV") (class "Default")
      (node (ref "UNE") (pin "1") (pinfunction "OUTA_1") (pintype "output"))
      (node (ref "X-NORTH") (pin "11") (pinfunction "11_11") (pintype "bidirectional"))
    )
    (net (code "102") (name "N_VN") (class "Default")
      (node (ref "C31") (pin "1") (pinfunction "1_1") (pintype "passive"))
      (node (ref "C32") (pin "1") (pinfunction "1_1") (pintype "passive"))
      (node (ref "C33") (pin "1") (pinfunction "1_1") (pintype "passive"))
      (node (ref "C34") (pin "1") (pinfunction "1_1") (pintype "passive"))
      (node (ref "C35") (pin "1") (pinfunction "1_1") (pintype "passive"))
      (node (ref "C36") (pin "1") (pinfunction "1_1") (pintype "passive"))
      (node (ref "C37") (pin "1") (pinfunction "1_1") (pintype "passive"))
      (node (ref "C38") (pin "1") (pinfunction "1_1") (pintype "passive"))
      (node (ref "C39") (pin "1") (pinfunction "1_1") (pintype "passive"))
      (node (ref "C40") (pin "1") (pinfunction "1_1") (pintype "passive"))
      (node (ref "C41") (pin "1") (pinfunction "1_1") (pintype "passive"))
      (node (ref "C42") (pin "1") (pinfunction "1_1") (pintype "passive"))
      (node (ref "C43") (pin "1") (pinfunction "1_1") (pintype "passive"))
      (node (ref "C44") (pin "1") (pinfunction "1_1") (pintype "passive"))
      (node (ref "C68") (pin "1") (pinfunction "1_1") (pintype "passive"))
      (node (ref "C70") (pin "1") (pinfunction "1_1") (pintype "passive"))
      (node (ref "C78") (pin "1") (pinfunction "1_1") (pintype "passive"))
      (node (ref "C79") (pin "1") (pinfunction "1_1") (pintype "passive"))
      (node (ref "C80") (pin "1") (pinfunction "1_1") (pintype "passive"))
      (node (ref "C87") (pin "1") (pinfunction "1_1") (pintype "passive"))
      (node (ref "C88") (pin "1") (pinfunction "1_1") (pintype "passive"))
      (node (ref "C89") (pin "1") (pinfunction "1_1") (pintype "passive"))
      (node (ref "TP5") (pin "TP") (pinfunction "TP_TP") (pintype "input"))
      (node (ref "U$2") (pin "A10") (pinfunction "VDD18_A10") (pintype "power_in"))
      (node (ref "U$2") (pin "A15") (pinfunction "VDD18_A15") (pintype "power_in"))
      (node (ref "U$2") (pin "A16") (pinfunction "VDD18_A16") (pintype "power_in"))
      (node (ref "U$2") (pin "A22") (pinfunction "VDD18_A22") (pintype "power_in"))
      (node (ref "U$2") (pin "A26") (pinfunction "VDD18_A26") (pintype "power_in"))
      (node (ref "U$2") (pin "A27") (pinfunction "VDD18_A27") (pintype "power_in"))
      (node (ref "U$2") (pin "B4") (pinfunction "VDD18_B4") (pintype "power_in"))
      (node (ref "U$2") (pin "E1") (pinfunction "VDD18_PLL_E1") (pintype "power_in"))
      (node (ref "U$2") (pin "H10") (pinfunction "VDD18_H10") (pintype "power_in"))
      (node (ref "U$2") (pin "H15") (pinfunction "VDD18_H15") (pintype "power_in"))
      (node (ref "U$2") (pin "H16") (pinfunction "VDD18_H16") (pintype "power_in"))
      (node (ref "U$2") (pin "H22") (pinfunction "VDD18_H22") (pintype "power_in"))
      (node (ref "U$2") (pin "H26") (pinfunction "VDD18_H26") (pintype "power_in"))
      (node (ref "U$2") (pin "H5") (pinfunction "VDD18_H5") (pintype "power_in"))
      (node (ref "U5") (pin "14") (pinfunction "VCCA_14") (pintype "power_in"))
      (node (ref "U5") (pin "15") (pinfunction "DIR1_15") (pintype "input"))
      (node (ref "U5") (pin "16") (pinfunction "DIR2_16") (pintype "input"))
      (node (ref "U5") (pin "5") (pinfunction "DIR3_5") (pintype "input"))
      (node (ref "U6") (pin "14") (pinfunction "VCCA_14") (pintype "power_in"))
      (node (ref "U6") (pin "16") (pinfunction "DIR2_16") (pintype "input"))
      (node (ref "X-NORTH") (pin "49") (pinfunction "49_49") (pintype "bidirectional"))
      (node (ref "X-NORTH") (pin "55") (pinfunction "55_55") (pintype "bidirectional"))
      (node (ref "X-NORTH") (pin "61") (pinfunction "61_61") (pintype "bidirectional"))
      (node (ref "X-NORTH") (pin "67") (pinfunction "67_67") (pintype "bidirectional"))
      (node (ref "X-NORTH") (pin "73") (pinfunction "73_73") (pintype "bidirectional"))
      (node (ref "X-NORTH") (pin "79") (pinfunction "79_79") (pintype "bidirectional"))
      (node (ref "X-NORTH") (pin "85") (pinfunction "85_85") (pintype "bidirectional"))
      (node (ref "X-NORTH") (pin "91") (pinfunction "91_91") (pintype "bidirectional"))
      (node (ref "X-NORTH") (pin "97") (pinfunction "97_97") (pintype "bidirectional"))
    )
    (net (code "103") (name "N_VN_CV") (class "Default")
      (node (ref "C9") (pin "1") (pinfunction "1_1") (pintype "passive"))
      (node (ref "R4") (pin "1") (pinfunction "1_1") (pintype "passive"))
      (node (ref "X-NORTH") (pin "4") (pinfunction "4_4") (pintype "bidirectional"))
    )
    (net (code "104") (name "N_VN_OV") (class "Default")
      (node (ref "UNN") (pin "7") (pinfunction "OUTB_7") (pintype "output"))
      (node (ref "X-NORTH") (pin "3") (pinfunction "3_3") (pintype "bidirectional"))
    )
    (net (code "105") (name "N_VN_UV") (class "Default")
      (node (ref "UNN") (pin "1") (pinfunction "OUTA_1") (pintype "output"))
      (node (ref "X-NORTH") (pin "9") (pinfunction "9_9") (pintype "bidirectional"))
    )
    (net (code "106") (name "N_VW") (class "Default")
      (node (ref "C57") (pin "1") (pinfunction "1_1") (pintype "passive"))
      (node (ref "C58") (pin "1") (pinfunction "1_1") (pintype "passive"))
      (node (ref "C59") (pin "1") (pinfunction "1_1") (pintype "passive"))
      (node (ref "TP8") (pin "TP") (pinfunction "TP_TP") (pintype "input"))
      (node (ref "U$2") (pin "E2") (pinfunction "VDD_RES_E2") (pintype "power_in"))
      (node (ref "U$2") (pin "G4") (pinfunction "VDD_RES_G4") (pintype "power_in"))
      (node (ref "X-NORTH") (pin "13") (pinfunction "13_13") (pintype "bidirectional"))
      (node (ref "X-NORTH") (pin "19") (pinfunction "19_19") (pintype "bidirectional"))
      (node (ref "X-NORTH") (pin "25") (pinfunction "25_25") (pintype "bidirectional"))
      (node (ref "X-NORTH") (pin "31") (pinfunction "31_31") (pintype "bidirectional"))
      (node (ref "X-NORTH") (pin "37") (pinfunction "37_37") (pintype "bidirectional"))
      (node (ref "X-NORTH") (pin "43") (pinfunction "43_43") (pintype "bidirectional"))
    )
    (net (code "107") (name "N_VW_CV") (class "Default")
      (node (ref "C8") (pin "1") (pinfunction "1_1") (pintype "passive"))
      (node (ref "R1") (pin "1") (pinfunction "1_1") (pintype "passive"))
      (node (ref "X-NORTH") (pin "2") (pinfunction "2_2") (pintype "bidirectional"))
    )
    (net (code "108") (name "N_VW_OV") (class "Default")
      (node (ref "UNW") (pin "7") (pinfunction "OUTB_7") (pintype "output"))
      (node (ref "X-NORTH") (pin "1") (pinfunction "1_1") (pintype "bidirectional"))
    )
    (net (code "109") (name "N_VW_UV") (class "Default")
      (node (ref "UNW") (pin "1") (pinfunction "OUTA_1") (pintype "output"))
      (node (ref "X-NORTH") (pin "7") (pinfunction "7_7") (pintype "bidirectional"))
    )
    (net (code "110") (name "Net-(U$2B-CMDN)") (class "Default")
      (node (ref "C119") (pin "1") (pinfunction "1_1") (pintype "passive"))
      (node (ref "U$2") (pin "F1") (pinfunction "CMDN_F1") (pintype "bidirectional"))
    )
    (net (code "111") (name "Net-(U$2B-CMDP)") (class "Default")
      (node (ref "C22") (pin "2") (pinfunction "2_2") (pintype "passive"))
      (node (ref "U$2") (pin "F2") (pinfunction "CMDP_F2") (pintype "bidirectional"))
    )
    (net (code "112") (name "Net-(U$2B-CMDP_COMP)") (class "Default")
      (node (ref "C28") (pin "2") (pinfunction "2_2") (pintype "passive"))
      (node (ref "U$2") (pin "H3") (pinfunction "CMDP_COMP_H3") (pintype "bidirectional"))
    )
    (net (code "113") (name "Net-(U$2B-CMDP_COMP_INV)") (class "Default")
      (node (ref "C27") (pin "2") (pinfunction "2_2") (pintype "passive"))
      (node (ref "U$2") (pin "F3") (pinfunction "CMDP_COMP_INV_F3") (pintype "bidirectional"))
    )
    (net (code "114") (name "Net-(U$2B-CMD_COLAMP)") (class "Default")
      (node (ref "C25") (pin "2") (pinfunction "2_2") (pintype "passive"))
      (node (ref "U$2") (pin "C6") (pinfunction "CMD_COLAMP_C6") (pintype "bidirectional"))
    )
    (net (code "115") (name "Net-(U$2B-CMD_COL_LOAD)") (class "Default")
      (node (ref "C23") (pin "2") (pinfunction "2_2") (pintype "passive"))
      (node (ref "U$2") (pin "B1") (pinfunction "CMD_COL_LOAD_B1") (pintype "bidirectional"))
    )
    (net (code "116") (name "Net-(U$2B-CMD_COL_PC)") (class "Default")
      (node (ref "C26") (pin "2") (pinfunction "2_2") (pintype "passive"))
      (node (ref "U$2") (pin "D1") (pinfunction "CMD_COL_PC_D1") (pintype "bidirectional"))
    )
    (net (code "117") (name "Net-(U$2B-CMD_LVDS)") (class "Default")
      (node (ref "C120") (pin "1") (pinfunction "1_1") (pintype "passive"))
      (node (ref "U$2") (pin "C1") (pinfunction "CMD_LVDS_C1") (pintype "bidirectional"))
    )
    (net (code "118") (name "Net-(U$2B-CMD_RAMP)") (class "Default")
      (node (ref "C24") (pin "2") (pinfunction "2_2") (pintype "passive"))
      (node (ref "U$2") (pin "B29") (pinfunction "CMD_RAMP_B29") (pintype "bidirectional"))
    )
    (net (code "119") (name "Net-(U$2B-VBGAP)") (class "Default")
      (node (ref "C122") (pin "1") (pinfunction "1_1") (pintype "passive"))
      (node (ref "U$2") (pin "C29") (pinfunction "VBGAP_C29") (pintype "bidirectional"))
    )
    (net (code "120") (name "Net-(U$2B-VCLAMP)") (class "Default")
      (node (ref "C121") (pin "1") (pinfunction "1_1") (pintype "passive"))
      (node (ref "U$2") (pin "D4") (pinfunction "VCLAMP_D4") (pintype "bidirectional"))
    )
    (net (code "121") (name "Net-(U$2B-VCLAMP_ADC)") (class "Default")
      (node (ref "C118") (pin "1") (pinfunction "1_1") (pintype "passive"))
      (node (ref "U$2") (pin "G2") (pinfunction "VCLAMP_ADC_G2") (pintype "bidirectional"))
    )
    (net (code "122") (name "Net-(U$2B-VPCH_H)") (class "Default")
      (node (ref "C123") (pin "1") (pinfunction "1_1") (pintype "passive"))
      (node (ref "U$2") (pin "C4") (pinfunction "VPCH_H_C4") (pintype "bidirectional"))
    )
    (net (code "123") (name "Net-(U$2B-VPCH_L)") (class "Default")
      (node (ref "C14") (pin "1") (pinfunction "1_1") (pintype "passive"))
      (node (ref "U$2") (pin "A4") (pinfunction "VPCH_L_A4") (pintype "bidirectional"))
    )
    (net (code "124") (name "Net-(U$2B-VREF)") (class "Default")
      (node (ref "C29") (pin "1") (pinfunction "1_1") (pintype "passive"))
      (node (ref "U$2") (pin "A3") (pinfunction "VREF_A3") (pintype "bidirectional"))
    )
    (net (code "125") (name "Net-(U$2B-VREF_ADC)") (class "Default")
      (node (ref "C30") (pin "1") (pinfunction "1_1") (pintype "passive"))
      (node (ref "U$2") (pin "B3") (pinfunction "VREF_ADC_B3") (pintype "bidirectional"))
    )
    (net (code "126") (name "Net-(U$2B-VRES_L)") (class "Default")
      (node (ref "C15") (pin "1") (pinfunction "1_1") (pintype "passive"))
      (node (ref "U$2") (pin "D5") (pinfunction "VRES_L_D5") (pintype "bidirectional"))
    )
    (net (code "127") (name "Net-(U$2B-VTF_LOW0)") (class "Default")
      (node (ref "C18") (pin "1") (pinfunction "1_1") (pintype "passive"))
      (node (ref "U$2") (pin "C5") (pinfunction "VTF_LOW0_C5") (pintype "bidirectional"))
    )
    (net (code "128") (name "Net-(U$2B-VTF_LOW1)") (class "Default")
      (node (ref "C19") (pin "1") (pinfunction "1_1") (pintype "passive"))
      (node (ref "U$2") (pin "D6") (pinfunction "VTF_LOW1_D6") (pintype "bidirectional"))
    )
    (net (code "129") (name "Net-(U$2B-VTF_LOW2)") (class "Default")
      (node (ref "C20") (pin "1") (pinfunction "1_1") (pintype "passive"))
      (node (ref "U$2") (pin "B30") (pinfunction "VTF_LOW2_B30") (pintype "bidirectional"))
    )
    (net (code "130") (name "Net-(U$2B-VTF_LOW3)") (class "Default")
      (node (ref "C21") (pin "1") (pinfunction "1_1") (pintype "passive"))
      (node (ref "U$2") (pin "C30") (pinfunction "VTF_LOW3_C30") (pintype "bidirectional"))
    )
    (net (code "131") (name "Net-(U$4-ADJ)") (class "Default")
      (node (ref "R21") (pin "1") (pinfunction "1_1") (pintype "passive"))
      (node (ref "R22") (pin "2") (pinfunction "2_2") (pintype "passive"))
      (node (ref "U$4") (pin "5") (pinfunction "ADJ_5") (pintype "input"))
    )
    (net (code "132") (name "Net-(UEP-WP)") (class "Default")
      (node (ref "R1X") (pin "2") (pinfunction "2_2") (pintype "passive"))
      (node (ref "R2X") (pin "1") (pinfunction "1_1") (pintype "passive"))
      (node (ref "UEP") (pin "7") (pinfunction "WP_7") (pintype "input"))
    )
    (net (code "133") (name "Net-(UNE-VINA+)") (class "Default")
      (node (ref "R7") (pin "2") (pinfunction "2_2") (pintype "passive"))
      (node (ref "R8") (pin "1") (pinfunction "1_1") (pintype "passive"))
      (node (ref "UNE") (pin "3") (pinfunction "VINA+_3") (pintype "input"))
    )
    (net (code "134") (name "Net-(UNE-VINB-)") (class "Default")
      (node (ref "R8") (pin "2") (pinfunction "2_2") (pintype "passive"))
      (node (ref "R9") (pin "1") (pinfunction "1_1") (pintype "passive"))
      (node (ref "UNE") (pin "6") (pinfunction "VINB-_6") (pintype "input"))
    )
    (net (code "135") (name "Net-(UNN-VINA+)") (class "Default")
      (node (ref "R4") (pin "2") (pinfunction "2_2") (pintype "passive"))
      (node (ref "R5") (pin "1") (pinfunction "1_1") (pintype "passive"))
      (node (ref "UNN") (pin "3") (pinfunction "VINA+_3") (pintype "input"))
    )
    (net (code "136") (name "Net-(UNN-VINB-)") (class "Default")
      (node (ref "R5") (pin "2") (pinfunction "2_2") (pintype "passive"))
      (node (ref "R6") (pin "1") (pinfunction "1_1") (pintype "passive"))
      (node (ref "UNN") (pin "6") (pinfunction "VINB-_6") (pintype "input"))
    )
    (net (code "137") (name "Net-(UNW-VINA+)") (class "Default")
      (node (ref "R1") (pin "2") (pinfunction "2_2") (pintype "passive"))
      (node (ref "R2") (pin "1") (pinfunction "1_1") (pintype "passive"))
      (node (ref "UNW") (pin "3") (pinfunction "VINA+_3") (pintype "input"))
    )
    (net (code "138") (name "Net-(UNW-VINB-)") (class "Default")
      (node (ref "R2") (pin "2") (pinfunction "2_2") (pintype "passive"))
      (node (ref "R3") (pin "1") (pinfunction "1_1") (pintype "passive"))
      (node (ref "UNW") (pin "6") (pinfunction "VINB-_6") (pintype "input"))
    )
    (net (code "139") (name "Net-(USE-VINA+)") (class "Default")
      (node (ref "R10") (pin "2") (pinfunction "2_2") (pintype "passive"))
      (node (ref "R11") (pin "1") (pinfunction "1_1") (pintype "passive"))
      (node (ref "USE") (pin "3") (pinfunction "VINA+_3") (pintype "input"))
    )
    (net (code "140") (name "Net-(USE-VINB-)") (class "Default")
      (node (ref "R11") (pin "2") (pinfunction "2_2") (pintype "passive"))
      (node (ref "R12") (pin "1") (pinfunction "1_1") (pintype "passive"))
      (node (ref "USE") (pin "6") (pinfunction "VINB-_6") (pintype "input"))
    )
    (net (code "141") (name "Net-(USS-VINA+)") (class "Default")
      (node (ref "R13") (pin "2") (pinfunction "2_2") (pintype "passive"))
      (node (ref "R14") (pin "1") (pinfunction "1_1") (pintype "passive"))
      (node (ref "USS") (pin "3") (pinfunction "VINA+_3") (pintype "input"))
    )
    (net (code "142") (name "Net-(USS-VINB-)") (class "Default")
      (node (ref "R14") (pin "2") (pinfunction "2_2") (pintype "passive"))
      (node (ref "R15") (pin "1") (pinfunction "1_1") (pintype "passive"))
      (node (ref "USS") (pin "6") (pinfunction "VINB-_6") (pintype "input"))
    )
    (net (code "143") (name "Net-(USW-VINA+)") (class "Default")
      (node (ref "R16") (pin "2") (pinfunction "2_2") (pintype "passive"))
      (node (ref "R17") (pin "1") (pinfunction "1_1") (pintype "passive"))
      (node (ref "USW") (pin "3") (pinfunction "VINA+_3") (pintype "input"))
    )
    (net (code "144") (name "Net-(USW-VINB-)") (class "Default")
      (node (ref "R17") (pin "2") (pinfunction "2_2") (pintype "passive"))
      (node (ref "R18") (pin "1") (pinfunction "1_1") (pintype "passive"))
      (node (ref "USW") (pin "6") (pinfunction "VINB-_6") (pintype "input"))
    )
    (net (code "145") (name "S00_N") (class "Default")
      (node (ref "X-SOUTH") (pin "16") (pinfunction "16_16") (pintype "bidirectional"))
    )
    (net (code "146") (name "S00_P") (class "Default")
      (node (ref "X-SOUTH") (pin "14") (pinfunction "14_14") (pintype "bidirectional"))
    )
    (net (code "147") (name "S01_N") (class "Default")
      (node (ref "X-SOUTH") (pin "17") (pinfunction "17_17") (pintype "bidirectional"))
    )
    (net (code "148") (name "S01_P") (class "Default")
      (node (ref "X-SOUTH") (pin "15") (pinfunction "15_15") (pintype "bidirectional"))
    )
    (net (code "149") (name "S02_N") (class "Default")
      (node (ref "X-SOUTH") (pin "22") (pinfunction "22_22") (pintype "bidirectional"))
    )
    (net (code "150") (name "S02_P") (class "Default")
      (node (ref "X-SOUTH") (pin "20") (pinfunction "20_20") (pintype "bidirectional"))
    )
    (net (code "151") (name "S03_N") (class "Default")
      (node (ref "X-SOUTH") (pin "23") (pinfunction "23_23") (pintype "bidirectional"))
    )
    (net (code "152") (name "S03_P") (class "Default")
      (node (ref "X-SOUTH") (pin "21") (pinfunction "21_21") (pintype "bidirectional"))
    )
    (net (code "153") (name "S04_N") (class "Default")
      (node (ref "U$2") (pin "C24") (pinfunction "OUT32_N_C24") (pintype "output"))
      (node (ref "X-SOUTH") (pin "28") (pinfunction "28_28") (pintype "bidirectional"))
    )
    (net (code "154") (name "S04_P") (class "Default")
      (node (ref "U$2") (pin "C25") (pinfunction "OUT32_P_C25") (pintype "output"))
      (node (ref "X-SOUTH") (pin "26") (pinfunction "26_26") (pintype "bidirectional"))
    )
    (net (code "155") (name "S05_N") (class "Default")
      (node (ref "X-SOUTH") (pin "29") (pinfunction "29_29") (pintype "bidirectional"))
    )
    (net (code "156") (name "S05_P") (class "Default")
      (node (ref "X-SOUTH") (pin "27") (pinfunction "27_27") (pintype "bidirectional"))
    )
    (net (code "157") (name "S06_N") (class "Default")
      (node (ref "U$2") (pin "D23") (pinfunction "OUT30_N_D23") (pintype "output"))
      (node (ref "X-SOUTH") (pin "34") (pinfunction "34_34") (pintype "bidirectional"))
    )
    (net (code "158") (name "S06_P") (class "Default")
      (node (ref "U$2") (pin "D24") (pinfunction "OUT30_P_D24") (pintype "output"))
      (node (ref "X-SOUTH") (pin "32") (pinfunction "32_32") (pintype "bidirectional"))
    )
    (net (code "159") (name "S07_N") (class "Default")
      (node (ref "U$2") (pin "B24") (pinfunction "OUT31_N_B24") (pintype "output"))
      (node (ref "X-SOUTH") (pin "35") (pinfunction "35_35") (pintype "bidirectional"))
    )
    (net (code "160") (name "S07_P") (class "Default")
      (node (ref "U$2") (pin "B25") (pinfunction "OUT31_P_B25") (pintype "output"))
      (node (ref "X-SOUTH") (pin "33") (pinfunction "33_33") (pintype "bidirectional"))
    )
    (net (code "161") (name "S08_N") (class "Default")
      (node (ref "U$2") (pin "D21") (pinfunction "OUT27_N_D21") (pintype "output"))
      (node (ref "X-SOUTH") (pin "40") (pinfunction "40_40") (pintype "bidirectional"))
    )
    (net (code "162") (name "S08_P") (class "Default")
      (node (ref "U$2") (pin "D22") (pinfunction "OUT27_P_D22") (pintype "output"))
      (node (ref "X-SOUTH") (pin "38") (pinfunction "38_38") (pintype "bidirectional"))
    )
    (net (code "163") (name "S09_N") (class "Default")
      (node (ref "U$2") (pin "A23") (pinfunction "OUT29_N_A23") (pintype "output"))
      (node (ref "X-SOUTH") (pin "41") (pinfunction "41_41") (pintype "bidirectional"))
    )
    (net (code "164") (name "S09_P") (class "Default")
      (node (ref "U$2") (pin "A24") (pinfunction "OUT29_P_A24") (pintype "output"))
      (node (ref "X-SOUTH") (pin "39") (pinfunction "39_39") (pintype "bidirectional"))
    )
    (net (code "165") (name "S10_N") (class "Default")
      (node (ref "U$2") (pin "C21") (pinfunction "OUT28_N_C21") (pintype "output"))
      (node (ref "X-SOUTH") (pin "46") (pinfunction "46_46") (pintype "bidirectional"))
    )
    (net (code "166") (name "S10_P") (class "Default")
      (node (ref "U$2") (pin "C22") (pinfunction "OUT28_P_C22") (pintype "output"))
      (node (ref "X-SOUTH") (pin "44") (pinfunction "44_44") (pintype "bidirectional"))
    )
    (net (code "167") (name "S11_N") (class "Default")
      (node (ref "U$2") (pin "B20") (pinfunction "OUT26_N_B20") (pintype "output"))
      (node (ref "X-SOUTH") (pin "47") (pinfunction "47_47") (pintype "bidirectional"))
    )
    (net (code "168") (name "S11_P") (class "Default")
      (node (ref "U$2") (pin "B21") (pinfunction "OUT26_P_B21") (pintype "output"))
      (node (ref "X-SOUTH") (pin "45") (pinfunction "45_45") (pintype "bidirectional"))
    )
    (net (code "169") (name "S12_N") (class "Default")
      (node (ref "U$2") (pin "D19") (pinfunction "OUT24_N_D19") (pintype "output"))
      (node (ref "X-SOUTH") (pin "52") (pinfunction "52_52") (pintype "bidirectional"))
    )
    (net (code "170") (name "S12_P") (class "Default")
      (node (ref "U$2") (pin "D20") (pinfunction "OUT24_P_D20") (pintype "output"))
      (node (ref "X-SOUTH") (pin "50") (pinfunction "50_50") (pintype "bidirectional"))
    )
    (net (code "171") (name "S13_N") (class "Default")
      (node (ref "U$2") (pin "A19") (pinfunction "OUT23_N_A19") (pintype "output"))
      (node (ref "X-SOUTH") (pin "53") (pinfunction "53_53") (pintype "bidirectional"))
    )
    (net (code "172") (name "S13_P") (class "Default")
      (node (ref "U$2") (pin "A20") (pinfunction "OUT23_P_A20") (pintype "output"))
      (node (ref "X-SOUTH") (pin "51") (pinfunction "51_51") (pintype "bidirectional"))
    )
    (net (code "173") (name "S14_N") (class "Default")
      (node (ref "U$2") (pin "C19") (pinfunction "OUT25_N_C19") (pintype "output"))
      (node (ref "X-SOUTH") (pin "58") (pinfunction "58_58") (pintype "bidirectional"))
    )
    (net (code "174") (name "S14_P") (class "Default")
      (node (ref "U$2") (pin "C20") (pinfunction "OUT25_P_C20") (pintype "output"))
      (node (ref "X-SOUTH") (pin "56") (pinfunction "56_56") (pintype "bidirectional"))
    )
    (net (code "175") (name "S15_N") (class "Default")
      (node (ref "U$2") (pin "B18") (pinfunction "OUT22_N_B18") (pintype "output"))
      (node (ref "X-SOUTH") (pin "59") (pinfunction "59_59") (pintype "bidirectional"))
    )
    (net (code "176") (name "S15_P") (class "Default")
      (node (ref "U$2") (pin "B19") (pinfunction "OUT22_P_B19") (pintype "output"))
      (node (ref "X-SOUTH") (pin "57") (pinfunction "57_57") (pintype "bidirectional"))
    )
    (net (code "177") (name "S16_N") (class "Default")
      (node (ref "U$2") (pin "C17") (pinfunction "OUT21_N_C17") (pintype "output"))
      (node (ref "X-SOUTH") (pin "64") (pinfunction "64_64") (pintype "bidirectional"))
    )
    (net (code "178") (name "S16_P") (class "Default")
      (node (ref "U$2") (pin "C18") (pinfunction "OUT21_P_C18") (pintype "output"))
      (node (ref "X-SOUTH") (pin "62") (pinfunction "62_62") (pintype "bidirectional"))
    )
    (net (code "179") (name "S17_N") (class "Default")
      (node (ref "U$2") (pin "A17") (pinfunction "OUT19_N_A17") (pintype "output"))
      (node (ref "X-SOUTH") (pin "65") (pinfunction "65_65") (pintype "bidirectional"))
    )
    (net (code "180") (name "S17_P") (class "Default")
      (node (ref "U$2") (pin "A18") (pinfunction "OUT19_P_A18") (pintype "output"))
      (node (ref "X-SOUTH") (pin "63") (pinfunction "63_63") (pintype "bidirectional"))
    )
    (net (code "181") (name "S18_N") (class "Default")
      (node (ref "U$2") (pin "D17") (pinfunction "OUT20_N_D17") (pintype "output"))
      (node (ref "X-SOUTH") (pin "70") (pinfunction "70_70") (pintype "bidirectional"))
    )
    (net (code "182") (name "S18_P") (class "Default")
      (node (ref "U$2") (pin "D18") (pinfunction "OUT20_P_D18") (pintype "output"))
      (node (ref "X-SOUTH") (pin "68") (pinfunction "68_68") (pintype "bidirectional"))
    )
    (net (code "183") (name "S19_N") (class "Default")
      (node (ref "U$2") (pin "B16") (pinfunction "OUT18_N_B16") (pintype "output"))
      (node (ref "X-SOUTH") (pin "71") (pinfunction "71_71") (pintype "bidirectional"))
    )
    (net (code "184") (name "S19_P") (class "Default")
      (node (ref "U$2") (pin "B17") (pinfunction "OUT18_P_B17") (pintype "output"))
      (node (ref "X-SOUTH") (pin "69") (pinfunction "69_69") (pintype "bidirectional"))
    )
    (net (code "185") (name "S20_N") (class "Default")
      (node (ref "U$2") (pin "D15") (pinfunction "OUT17_N_D15") (pintype "output"))
      (node (ref "X-SOUTH") (pin "76") (pinfunction "76_76") (pintype "bidirectional"))
    )
    (net (code "186") (name "S20_P") (class "Default")
      (node (ref "U$2") (pin "D16") (pinfunction "OUT17_P_D16") (pintype "output"))
      (node (ref "X-SOUTH") (pin "74") (pinfunction "74_74") (pintype "bidirectional"))
    )
    (net (code "187") (name "S21_N") (class "Default")
      (node (ref "U$2") (pin "B14") (pinfunction "OUT16_N_B14") (pintype "output"))
      (node (ref "X-SOUTH") (pin "77") (pinfunction "77_77") (pintype "bidirectional"))
    )
    (net (code "188") (name "S21_P") (class "Default")
      (node (ref "U$2") (pin "B15") (pinfunction "OUT16_P_B15") (pintype "output"))
      (node (ref "X-SOUTH") (pin "75") (pinfunction "75_75") (pintype "bidirectional"))
    )
    (net (code "189") (name "S22_N") (class "Default")
      (node (ref "U$2") (pin "D13") (pinfunction "OUT15_N_D13") (pintype "output"))
      (node (ref "X-SOUTH") (pin "82") (pinfunction "82_82") (pintype "bidirectional"))
    )
    (net (code "190") (name "S22_P") (class "Default")
      (node (ref "U$2") (pin "D14") (pinfunction "OUT15_P_D14") (pintype "output"))
      (node (ref "X-SOUTH") (pin "80") (pinfunction "80_80") (pintype "bidirectional"))
    )
    (net (code "191") (name "S23_N") (class "Default")
      (node (ref "U$2") (pin "A13") (pinfunction "OUT13_N_A13") (pintype "output"))
      (node (ref "X-SOUTH") (pin "83") (pinfunction "83_83") (pintype "bidirectional"))
    )
    (net (code "192") (name "S23_P") (class "Default")
      (node (ref "U$2") (pin "A14") (pinfunction "OUT13_P_A14") (pintype "output"))
      (node (ref "X-SOUTH") (pin "81") (pinfunction "81_81") (pintype "bidirectional"))
    )
    (net (code "193") (name "S24_N") (class "Default")
      (node (ref "U$2") (pin "C13") (pinfunction "OUT14_N_C13") (pintype "output"))
      (node (ref "X-SOUTH") (pin "88") (pinfunction "88_88") (pintype "bidirectional"))
    )
    (net (code "194") (name "S24_P") (class "Default")
      (node (ref "U$2") (pin "C14") (pinfunction "OUT14_P_C14") (pintype "output"))
      (node (ref "X-SOUTH") (pin "86") (pinfunction "86_86") (pintype "bidirectional"))
    )
    (net (code "195") (name "S25_N") (class "Default")
      (node (ref "U$2") (pin "B12") (pinfunction "OUT12_N_B12") (pintype "output"))
      (node (ref "X-SOUTH") (pin "89") (pinfunction "89_89") (pintype "bidirectional"))
    )
    (net (code "196") (name "S25_P") (class "Default")
      (node (ref "U$2") (pin "B13") (pinfunction "OUT12_P_B13") (pintype "output"))
      (node (ref "X-SOUTH") (pin "87") (pinfunction "87_87") (pintype "bidirectional"))
    )
    (net (code "197") (name "S26_N") (class "Default")
      (node (ref "U$2") (pin "D11") (pinfunction "OUT10_N_D11") (pintype "output"))
      (node (ref "X-SOUTH") (pin "94") (pinfunction "94_94") (pintype "bidirectional"))
    )
    (net (code "198") (name "S26_P") (class "Default")
      (node (ref "U$2") (pin "D12") (pinfunction "OUT10_P_D12") (pintype "output"))
      (node (ref "X-SOUTH") (pin "92") (pinfunction "92_92") (pintype "bidirectional"))
    )
    (net (code "199") (name "S27_N") (class "Default")
      (node (ref "U$2") (pin "A11") (pinfunction "OUT9_N_A11") (pintype "output"))
      (node (ref "X-SOUTH") (pin "95") (pinfunction "95_95") (pintype "bidirectional"))
    )
    (net (code "200") (name "S27_P") (class "Default")
      (node (ref "U$2") (pin "A12") (pinfunction "OUT9_P_A12") (pintype "output"))
      (node (ref "X-SOUTH") (pin "93") (pinfunction "93_93") (pintype "bidirectional"))
    )
    (net (code "201") (name "S28_N") (class "Default")
      (node (ref "U$2") (pin "C11") (pinfunction "OUT11_N_C11") (pintype "output"))
      (node (ref "X-SOUTH") (pin "100") (pinfunction "100_100") (pintype "bidirectional"))
    )
    (net (code "202") (name "S28_P") (class "Default")
      (node (ref "U$2") (pin "C12") (pinfunction "OUT11_P_C12") (pintype "output"))
      (node (ref "X-SOUTH") (pin "98") (pinfunction "98_98") (pintype "bidirectional"))
    )
    (net (code "203") (name "S29_N") (class "Default")
      (node (ref "U$2") (pin "B10") (pinfunction "OUT8_N_B10") (pintype "output"))
      (node (ref "X-SOUTH") (pin "101") (pinfunction "101_101") (pintype "bidirectional"))
    )
    (net (code "204") (name "S29_P") (class "Default")
      (node (ref "U$2") (pin "B11") (pinfunction "OUT8_P_B11") (pintype "output"))
      (node (ref "X-SOUTH") (pin "99") (pinfunction "99_99") (pintype "bidirectional"))
    )
    (net (code "205") (name "S30_N") (class "Default")
      (node (ref "U$2") (pin "C9") (pinfunction "OUT7_N_C9") (pintype "output"))
      (node (ref "X-SOUTH") (pin "106") (pinfunction "106_106") (pintype "bidirectional"))
    )
    (net (code "206") (name "S30_P") (class "Default")
      (node (ref "U$2") (pin "C10") (pinfunction "OUT7_P_C10") (pintype "output"))
      (node (ref "X-SOUTH") (pin "104") (pinfunction "104_104") (pintype "bidirectional"))
    )
    (net (code "207") (name "S31_N") (class "Default")
      (node (ref "U$2") (pin "B8") (pinfunction "OUT5_N_B8") (pintype "output"))
      (node (ref "X-SOUTH") (pin "107") (pinfunction "107_107") (pintype "bidirectional"))
    )
    (net (code "208") (name "S31_P") (class "Default")
      (node (ref "U$2") (pin "B9") (pinfunction "OUT5_P_B9") (pintype "output"))
      (node (ref "X-SOUTH") (pin "105") (pinfunction "105_105") (pintype "bidirectional"))
    )
    (net (code "209") (name "S32_N") (class "Default")
      (node (ref "U$2") (pin "D9") (pinfunction "OUT6_N_D9") (pintype "output"))
      (node (ref "X-SOUTH") (pin "112") (pinfunction "112_112") (pintype "bidirectional"))
    )
    (net (code "210") (name "S32_P") (class "Default")
      (node (ref "U$2") (pin "D10") (pinfunction "OUT6_P_D10") (pintype "output"))
      (node (ref "X-SOUTH") (pin "110") (pinfunction "110_110") (pintype "bidirectional"))
    )
    (net (code "211") (name "S33_N") (class "Default")
      (node (ref "U$2") (pin "A7") (pinfunction "OUT2_N_A7") (pintype "output"))
      (node (ref "X-SOUTH") (pin "113") (pinfunction "113_113") (pintype "bidirectional"))
    )
    (net (code "212") (name "S33_P") (class "Default")
      (node (ref "U$2") (pin "A8") (pinfunction "OUT2_P_A8") (pintype "output"))
      (node (ref "X-SOUTH") (pin "111") (pinfunction "111_111") (pintype "bidirectional"))
    )
    (net (code "213") (name "S34_N") (class "Default")
      (node (ref "U$2") (pin "C7") (pinfunction "OUT4_N_C7") (pintype "output"))
      (node (ref "X-SOUTH") (pin "118") (pinfunction "118_118") (pintype "bidirectional"))
    )
    (net (code "214") (name "S34_P") (class "Default")
      (node (ref "U$2") (pin "C8") (pinfunction "OUT4_P_C8") (pintype "output"))
      (node (ref "X-SOUTH") (pin "116") (pinfunction "116_116") (pintype "bidirectional"))
    )
    (net (code "215") (name "S35_N") (class "Default")
      (node (ref "U$2") (pin "B6") (pinfunction "OUT1_N_B6") (pintype "output"))
      (node (ref "X-SOUTH") (pin "119") (pinfunction "119_119") (pintype "bidirectional"))
    )
    (net (code "216") (name "S35_P") (class "Default")
      (node (ref "U$2") (pin "B7") (pinfunction "OUT1_P_B7") (pintype "output"))
      (node (ref "X-SOUTH") (pin "117") (pinfunction "117_117") (pintype "bidirectional"))
    )
    (net (code "217") (name "S36_N") (class "Default")
      (node (ref "U$2") (pin "D7") (pinfunction "OUT3_N_D7") (pintype "output"))
      (node (ref "X-SOUTH") (pin "124") (pinfunction "124_124") (pintype "bidirectional"))
    )
    (net (code "218") (name "S36_P") (class "Default")
      (node (ref "U$2") (pin "D8") (pinfunction "OUT3_P_D8") (pintype "output"))
      (node (ref "X-SOUTH") (pin "122") (pinfunction "122_122") (pintype "bidirectional"))
    )
    (net (code "219") (name "S37_N") (class "Default")
      (node (ref "U$2") (pin "A5") (pinfunction "OUTCTR_N_A5") (pintype "output"))
      (node (ref "X-SOUTH") (pin "125") (pinfunction "125_125") (pintype "bidirectional"))
    )
    (net (code "220") (name "S37_P") (class "Default")
      (node (ref "U$2") (pin "A6") (pinfunction "OUTCTR_P_A6") (pintype "output"))
      (node (ref "X-SOUTH") (pin "123") (pinfunction "123_123") (pintype "bidirectional"))
    )
    (net (code "221") (name "S38_N") (class "Default")
      (node (ref "X-SOUTH") (pin "130") (pinfunction "130_130") (pintype "bidirectional"))
    )
    (net (code "222") (name "S38_P") (class "Default")
      (node (ref "X-SOUTH") (pin "128") (pinfunction "128_128") (pintype "bidirectional"))
    )
    (net (code "223") (name "S39_N") (class "Default")
      (node (ref "U$4") (pin "6") (pinfunction "EN_6") (pintype "input"))
      (node (ref "X-SOUTH") (pin "131") (pinfunction "131_131") (pintype "bidirectional"))
    )
    (net (code "224") (name "S39_P") (class "Default")
      (node (ref "X-SOUTH") (pin "129") (pinfunction "129_129") (pintype "bidirectional"))
    )
    (net (code "225") (name "SPI_CLK") (class "Default")
      (node (ref "U$2") (pin "H29") (pinfunction "SPI_CLK_H29") (pintype "input"))
      (node (ref "U4") (pin "6") (pinfunction "1A1_6") (pintype "output"))
    )
    (net (code "226") (name "SPI_EN") (class "Default")
      (node (ref "U$2") (pin "F28") (pinfunction "SPI_EN_F28") (pintype "input"))
      (node (ref "U6") (pin "9") (pinfunction "B4_9") (pintype "bidirectional"))
    )
    (net (code "227") (name "SPI_IN") (class "Default")
      (node (ref "U$2") (pin "E28") (pinfunction "SPI_IN_E28") (pintype "input"))
      (node (ref "U4") (pin "7") (pinfunction "1A2_7") (pintype "output"))
    )
    (net (code "228") (name "SPI_OUT") (class "Default")
      (node (ref "U$2") (pin "G28") (pinfunction "SPI_OUT_G28") (pintype "output"))
      (node (ref "U4") (pin "8") (pinfunction "2A1_8") (pintype "output"))
    )
    (net (code "229") (name "SYS_RES_N") (class "Default")
      (node (ref "U$2") (pin "F30") (pinfunction "SYS_RES_N_F30") (pintype "input"))
      (node (ref "U5") (pin "10") (pinfunction "B3_10") (pintype "bidirectional"))
    )
    (net (code "230") (name "S_CHK_V") (class "Default")
      (node (ref "C5") (pin "1") (pinfunction "1_1") (pintype "passive"))
      (node (ref "C6") (pin "1") (pinfunction "1_1") (pintype "passive"))
      (node (ref "C7") (pin "1") (pinfunction "1_1") (pintype "passive"))
      (node (ref "R20") (pin "1") (pinfunction "1_1") (pintype "passive"))
      (node (ref "TP3") (pin "TP") (pinfunction "TP_TP") (pintype "input"))
      (node (ref "USE") (pin "8") (pinfunction "VDD_8") (pintype "power_in"))
      (node (ref "USS") (pin "8") (pinfunction "VDD_8") (pintype "power_in"))
      (node (ref "USW") (pin "8") (pinfunction "VDD_8") (pintype "power_in"))
      (node (ref "X-SOUTH") (pin "10") (pinfunction "10_10") (pintype "bidirectional"))
      (node (ref "X-SOUTH") (pin "8") (pinfunction "8_8") (pintype "bidirectional"))
    )
    (net (code "231") (name "S_I2C_V") (class "Default")
      (node (ref "X-SOUTH") (pin "135") (pinfunction "135_135") (pintype "bidirectional"))
      (node (ref "X-SOUTH") (pin "137") (pinfunction "137_137") (pintype "bidirectional"))
    )
    (net (code "232") (name "S_REF") (class "Default")
      (node (ref "R20") (pin "2") (pinfunction "2_2") (pintype "passive"))
      (node (ref "TP4") (pin "TP") (pinfunction "TP_TP") (pintype "input"))
      (node (ref "U2") (pin "3") (pinfunction "CATHODE_3") (pintype "output"))
      (node (ref "U2") (pin "4") (pinfunction "REF_4") (pintype "input"))
      (node (ref "USE") (pin "2") (pinfunction "VINA-_2") (pintype "input"))
      (node (ref "USE") (pin "5") (pinfunction "VINB+_5") (pintype "input"))
      (node (ref "USS") (pin "2") (pinfunction "VINA-_2") (pintype "input"))
      (node (ref "USS") (pin "5") (pinfunction "VINB+_5") (pintype "input"))
      (node (ref "USW") (pin "2") (pinfunction "VINA-_2") (pintype "input"))
      (node (ref "USW") (pin "5") (pinfunction "VINB+_5") (pintype "input"))
    )
    (net (code "233") (name "S_SCK") (class "Default")
      (node (ref "X-SOUTH") (pin "144") (pinfunction "144_144") (pintype "bidirectional"))
    )
    (net (code "234") (name "S_SCL") (class "Default")
      (node (ref "X-SOUTH") (pin "143") (pinfunction "143_143") (pintype "bidirectional"))
    )
    (net (code "235") (name "S_SDA") (class "Default")
      (node (ref "X-SOUTH") (pin "141") (pinfunction "141_141") (pintype "bidirectional"))
    )
    (net (code "236") (name "S_SDI") (class "Default")
      (node (ref "X-SOUTH") (pin "140") (pinfunction "140_140") (pintype "bidirectional"))
    )
    (net (code "237") (name "S_SDO") (class "Default")
      (node (ref "X-SOUTH") (pin "142") (pinfunction "142_142") (pintype "bidirectional"))
    )
    (net (code "238") (name "S_SPI_V") (class "Default")
      (node (ref "X-SOUTH") (pin "134") (pinfunction "134_134") (pintype "bidirectional"))
      (node (ref "X-SOUTH") (pin "136") (pinfunction "136_136") (pintype "bidirectional"))
    )
    (net (code "239") (name "S_VE") (class "Default")
      (node (ref "X-SOUTH") (pin "13") (pinfunction "13_13") (pintype "bidirectional"))
      (node (ref "X-SOUTH") (pin "19") (pinfunction "19_19") (pintype "bidirectional"))
      (node (ref "X-SOUTH") (pin "25") (pinfunction "25_25") (pintype "bidirectional"))
      (node (ref "X-SOUTH") (pin "31") (pinfunction "31_31") (pintype "bidirectional"))
      (node (ref "X-SOUTH") (pin "37") (pinfunction "37_37") (pintype "bidirectional"))
      (node (ref "X-SOUTH") (pin "43") (pinfunction "43_43") (pintype "bidirectional"))
    )
    (net (code "240") (name "S_VE_CV") (class "Default")
      (node (ref "C11") (pin "1") (pinfunction "1_1") (pintype "passive"))
      (node (ref "R10") (pin "1") (pinfunction "1_1") (pintype "passive"))
      (node (ref "X-SOUTH") (pin "2") (pinfunction "2_2") (pintype "bidirectional"))
    )
    (net (code "241") (name "S_VE_OV") (class "Default")
      (node (ref "USE") (pin "7") (pinfunction "OUTB_7") (pintype "output"))
      (node (ref "X-SOUTH") (pin "1") (pinfunction "1_1") (pintype "bidirectional"))
    )
    (net (code "242") (name "S_VE_UV") (class "Default")
      (node (ref "USE") (pin "1") (pinfunction "OUTA_1") (pintype "output"))
      (node (ref "X-SOUTH") (pin "7") (pinfunction "7_7") (pintype "bidirectional"))
    )
    (net (code "243") (name "S_VS") (class "Default")
      (node (ref "C45") (pin "1") (pinfunction "1_1") (pintype "passive"))
      (node (ref "C46") (pin "1") (pinfunction "1_1") (pintype "passive"))
      (node (ref "C47") (pin "1") (pinfunction "1_1") (pintype "passive"))
      (node (ref "C48") (pin "1") (pinfunction "1_1") (pintype "passive"))
      (node (ref "C49") (pin "1") (pinfunction "1_1") (pintype "passive"))
      (node (ref "C72") (pin "1") (pinfunction "1_1") (pintype "passive"))
      (node (ref "C73") (pin "1") (pinfunction "1_1") (pintype "passive"))
      (node (ref "C74") (pin "1") (pinfunction "1_1") (pintype "passive"))
      (node (ref "C81") (pin "1") (pinfunction "1_1") (pintype "passive"))
      (node (ref "C82") (pin "1") (pinfunction "1_1") (pintype "passive"))
      (node (ref "C83") (pin "1") (pinfunction "1_1") (pintype "passive"))
      (node (ref "TP6") (pin "TP") (pinfunction "TP_TP") (pintype "input"))
      (node (ref "U$2") (pin "A30") (pinfunction "VDD_PIX_A30") (pintype "power_in"))
      (node (ref "U$2") (pin "D28") (pinfunction "VDD_PIX_D28") (pintype "power_in"))
      (node (ref "U$2") (pin "D30") (pinfunction "VDD_PIX_D30") (pintype "power_in"))
      (node (ref "U$2") (pin "G1") (pinfunction "VDD_PIX_G1") (pintype "power_in"))
      (node (ref "U$2") (pin "H28") (pinfunction "VDD_PIX_H28") (pintype "power_in"))
      (node (ref "X-SOUTH") (pin "49") (pinfunction "49_49") (pintype "bidirectional"))
      (node (ref "X-SOUTH") (pin "55") (pinfunction "55_55") (pintype "bidirectional"))
      (node (ref "X-SOUTH") (pin "61") (pinfunction "61_61") (pintype "bidirectional"))
      (node (ref "X-SOUTH") (pin "67") (pinfunction "67_67") (pintype "bidirectional"))
      (node (ref "X-SOUTH") (pin "73") (pinfunction "73_73") (pintype "bidirectional"))
      (node (ref "X-SOUTH") (pin "79") (pinfunction "79_79") (pintype "bidirectional"))
      (node (ref "X-SOUTH") (pin "85") (pinfunction "85_85") (pintype "bidirectional"))
      (node (ref "X-SOUTH") (pin "91") (pinfunction "91_91") (pintype "bidirectional"))
      (node (ref "X-SOUTH") (pin "97") (pinfunction "97_97") (pintype "bidirectional"))
    )
    (net (code "244") (name "S_VS_CV") (class "Default")
      (node (ref "C12") (pin "1") (pinfunction "1_1") (pintype "passive"))
      (node (ref "R13") (pin "1") (pinfunction "1_1") (pintype "passive"))
      (node (ref "X-SOUTH") (pin "4") (pinfunction "4_4") (pintype "bidirectional"))
    )
    (net (code "245") (name "S_VS_OV") (class "Default")
      (node (ref "USS") (pin "7") (pinfunction "OUTB_7") (pintype "output"))
      (node (ref "X-SOUTH") (pin "3") (pinfunction "3_3") (pintype "bidirectional"))
    )
    (net (code "246") (name "S_VS_UV") (class "Default")
      (node (ref "USS") (pin "1") (pinfunction "OUTA_1") (pintype "output"))
      (node (ref "X-SOUTH") (pin "9") (pinfunction "9_9") (pintype "bidirectional"))
    )
    (net (code "247") (name "S_VW") (class "Default")
      (node (ref "C90") (pin "1") (pinfunction "1_1") (pintype "passive"))
      (node (ref "U$4") (pin "1") (pinfunction "BIAS_1") (pintype "power_in"))
      (node (ref "U$4") (pin "3") (pinfunction "IN_3") (pintype "power_in"))
      (node (ref "X-SOUTH") (pin "103") (pinfunction "103_103") (pintype "bidirectional"))
      (node (ref "X-SOUTH") (pin "109") (pinfunction "109_109") (pintype "bidirectional"))
      (node (ref "X-SOUTH") (pin "115") (pinfunction "115_115") (pintype "bidirectional"))
      (node (ref "X-SOUTH") (pin "121") (pinfunction "121_121") (pintype "bidirectional"))
      (node (ref "X-SOUTH") (pin "127") (pinfunction "127_127") (pintype "bidirectional"))
      (node (ref "X-SOUTH") (pin "133") (pinfunction "133_133") (pintype "bidirectional"))
    )
    (net (code "248") (name "S_VW_CV") (class "Default")
      (node (ref "C13") (pin "1") (pinfunction "1_1") (pintype "passive"))
      (node (ref "R16") (pin "1") (pinfunction "1_1") (pintype "passive"))
      (node (ref "X-SOUTH") (pin "6") (pinfunction "6_6") (pintype "bidirectional"))
    )
    (net (code "249") (name "S_VW_OV") (class "Default")
      (node (ref "USW") (pin "7") (pinfunction "OUTB_7") (pintype "output"))
      (node (ref "X-SOUTH") (pin "5") (pinfunction "5_5") (pintype "bidirectional"))
    )
    (net (code "250") (name "S_VW_UV") (class "Default")
      (node (ref "USW") (pin "1") (pinfunction "OUTA_1") (pintype "output"))
      (node (ref "X-SOUTH") (pin "11") (pinfunction "11_11") (pintype "bidirectional"))
    )
    (net (code "251") (name "TDIG1") (class "Default")
      (node (ref "U$2") (pin "G27") (pinfunction "TDIG1_G27") (pintype "output"))
      (node (ref "U5") (pin "9") (pinfunction "B4_9") (pintype "bidirectional"))
    )
    (net (code "252") (name "TDIG2") (class "Default")
      (node (ref "U$2") (pin "G26") (pinfunction "TDIG2_G26") (pintype "output"))
      (node (ref "U6") (pin "11") (pinfunction "B2_11") (pintype "bidirectional"))
    )
    (net (code "253") (name "T_EXP1") (class "Default")
      (node (ref "U$2") (pin "H30") (pinfunction "T_EXP1_H30") (pintype "input"))
      (node (ref "U5") (pin "12") (pinfunction "B1_12") (pintype "bidirectional"))
    )
    (net (code "254") (name "T_EXP2") (class "Default")
      (node (ref "U$2") (pin "E29") (pinfunction "T_EXP2_E29") (pintype "input"))
      (node (ref "U6") (pin "10") (pinfunction "B3_10") (pintype "bidirectional"))
    )
    (net (code "255") (name "VRAMP1") (class "Default")
      (node (ref "C16") (pin "1") (pinfunction "1_1") (pintype "passive"))
      (node (ref "R23") (pin "1") (pinfunction "1_1") (pintype "passive"))
      (node (ref "U$2") (pin "G29") (pinfunction "VRAMP1_G29") (pintype "bidirectional"))
    )
    (net (code "256") (name "VRAMP2") (class "Default")
      (node (ref "C17") (pin "1") (pinfunction "1_1") (pintype "passive"))
      (node (ref "R23") (pin "2") (pinfunction "2_2") (pintype "passive"))
      (node (ref "U$2") (pin "F29") (pinfunction "VRAMP2_F29") (pintype "bidirectional"))
    )
    (net (code "257") (name "VTREF") (class "Default")
      (node (ref "C65") (pin "1") (pinfunction "1_1") (pintype "passive"))
      (node (ref "C91") (pin "2") (pinfunction "2_2") (pintype "passive"))
      (node (ref "R21") (pin "2") (pinfunction "2_2") (pintype "passive"))
      (node (ref "R24") (pin "1") (pinfunction "1_1") (pintype "passive"))
      (node (ref "U$2") (pin "B2") (pinfunction "VTREF_B2") (pintype "bidirectional"))
      (node (ref "U$4") (pin "4") (pinfunction "OUT_4") (pintype "power_in"))
    )
    (net (code "258") (name "VTSIG") (class "Default")
      (node (ref "C66") (pin "1") (pinfunction "1_1") (pintype "passive"))
      (node (ref "R24") (pin "2") (pinfunction "2_2") (pintype "passive"))
      (node (ref "U$2") (pin "C2") (pinfunction "VTSIG_C2") (pintype "bidirectional"))
    )
    (net (code "259") (name "unconnected-(U1-NC-Pad1)") (class "Default")
      (node (ref "U1") (pin "1") (pinfunction "NC_1") (pintype "no_connect"))
    )
    (net (code "260") (name "unconnected-(U1-NC-Pad2)") (class "Default")
      (node (ref "U1") (pin "2") (pinfunction "NC_2") (pintype "no_connect"))
    )
    (net (code "261") (name "unconnected-(U2-NC-Pad1)") (class "Default")
      (node (ref "U2") (pin "1") (pinfunction "NC_1") (pintype "no_connect"))
    )
    (net (code "262") (name "unconnected-(U2-NC-Pad2)") (class "Default")
      (node (ref "U2") (pin "2") (pinfunction "NC_2") (pintype "no_connect"))
    )
    (net (code "263") (name "unconnected-(U4-2B2-Pad12)") (class "Default")
      (node (ref "U4") (pin "12") (pinfunction "2B2_12") (pintype "output"))
    )
    (net (code "264") (name "unconnected-(X-NORTH-PadM1)") (class "Default")
      (node (ref "X-NORTH") (pin "M1") (pinfunction "M1_M1") (pintype "bidirectional"))
    )
    (net (code "265") (name "unconnected-(X-NORTH-PadM2)") (class "Default")
      (node (ref "X-NORTH") (pin "M2") (pinfunction "M2_M2") (pintype "bidirectional"))
    )
    (net (code "266") (name "unconnected-(X-SOUTH-PadM1)") (class "Default")
      (node (ref "X-SOUTH") (pin "M1") (pinfunction "M1_M1") (pintype "bidirectional"))
    )
    (net (code "267") (name "unconnected-(X-SOUTH-PadM2)") (class "Default")
      (node (ref "X-SOUTH") (pin "M2") (pinfunction "M2_M2") (pintype "bidirectional"))
    )
  )
)
